# Motor-Board.net
KiCad netlist of a schematic drawn in EAGLE
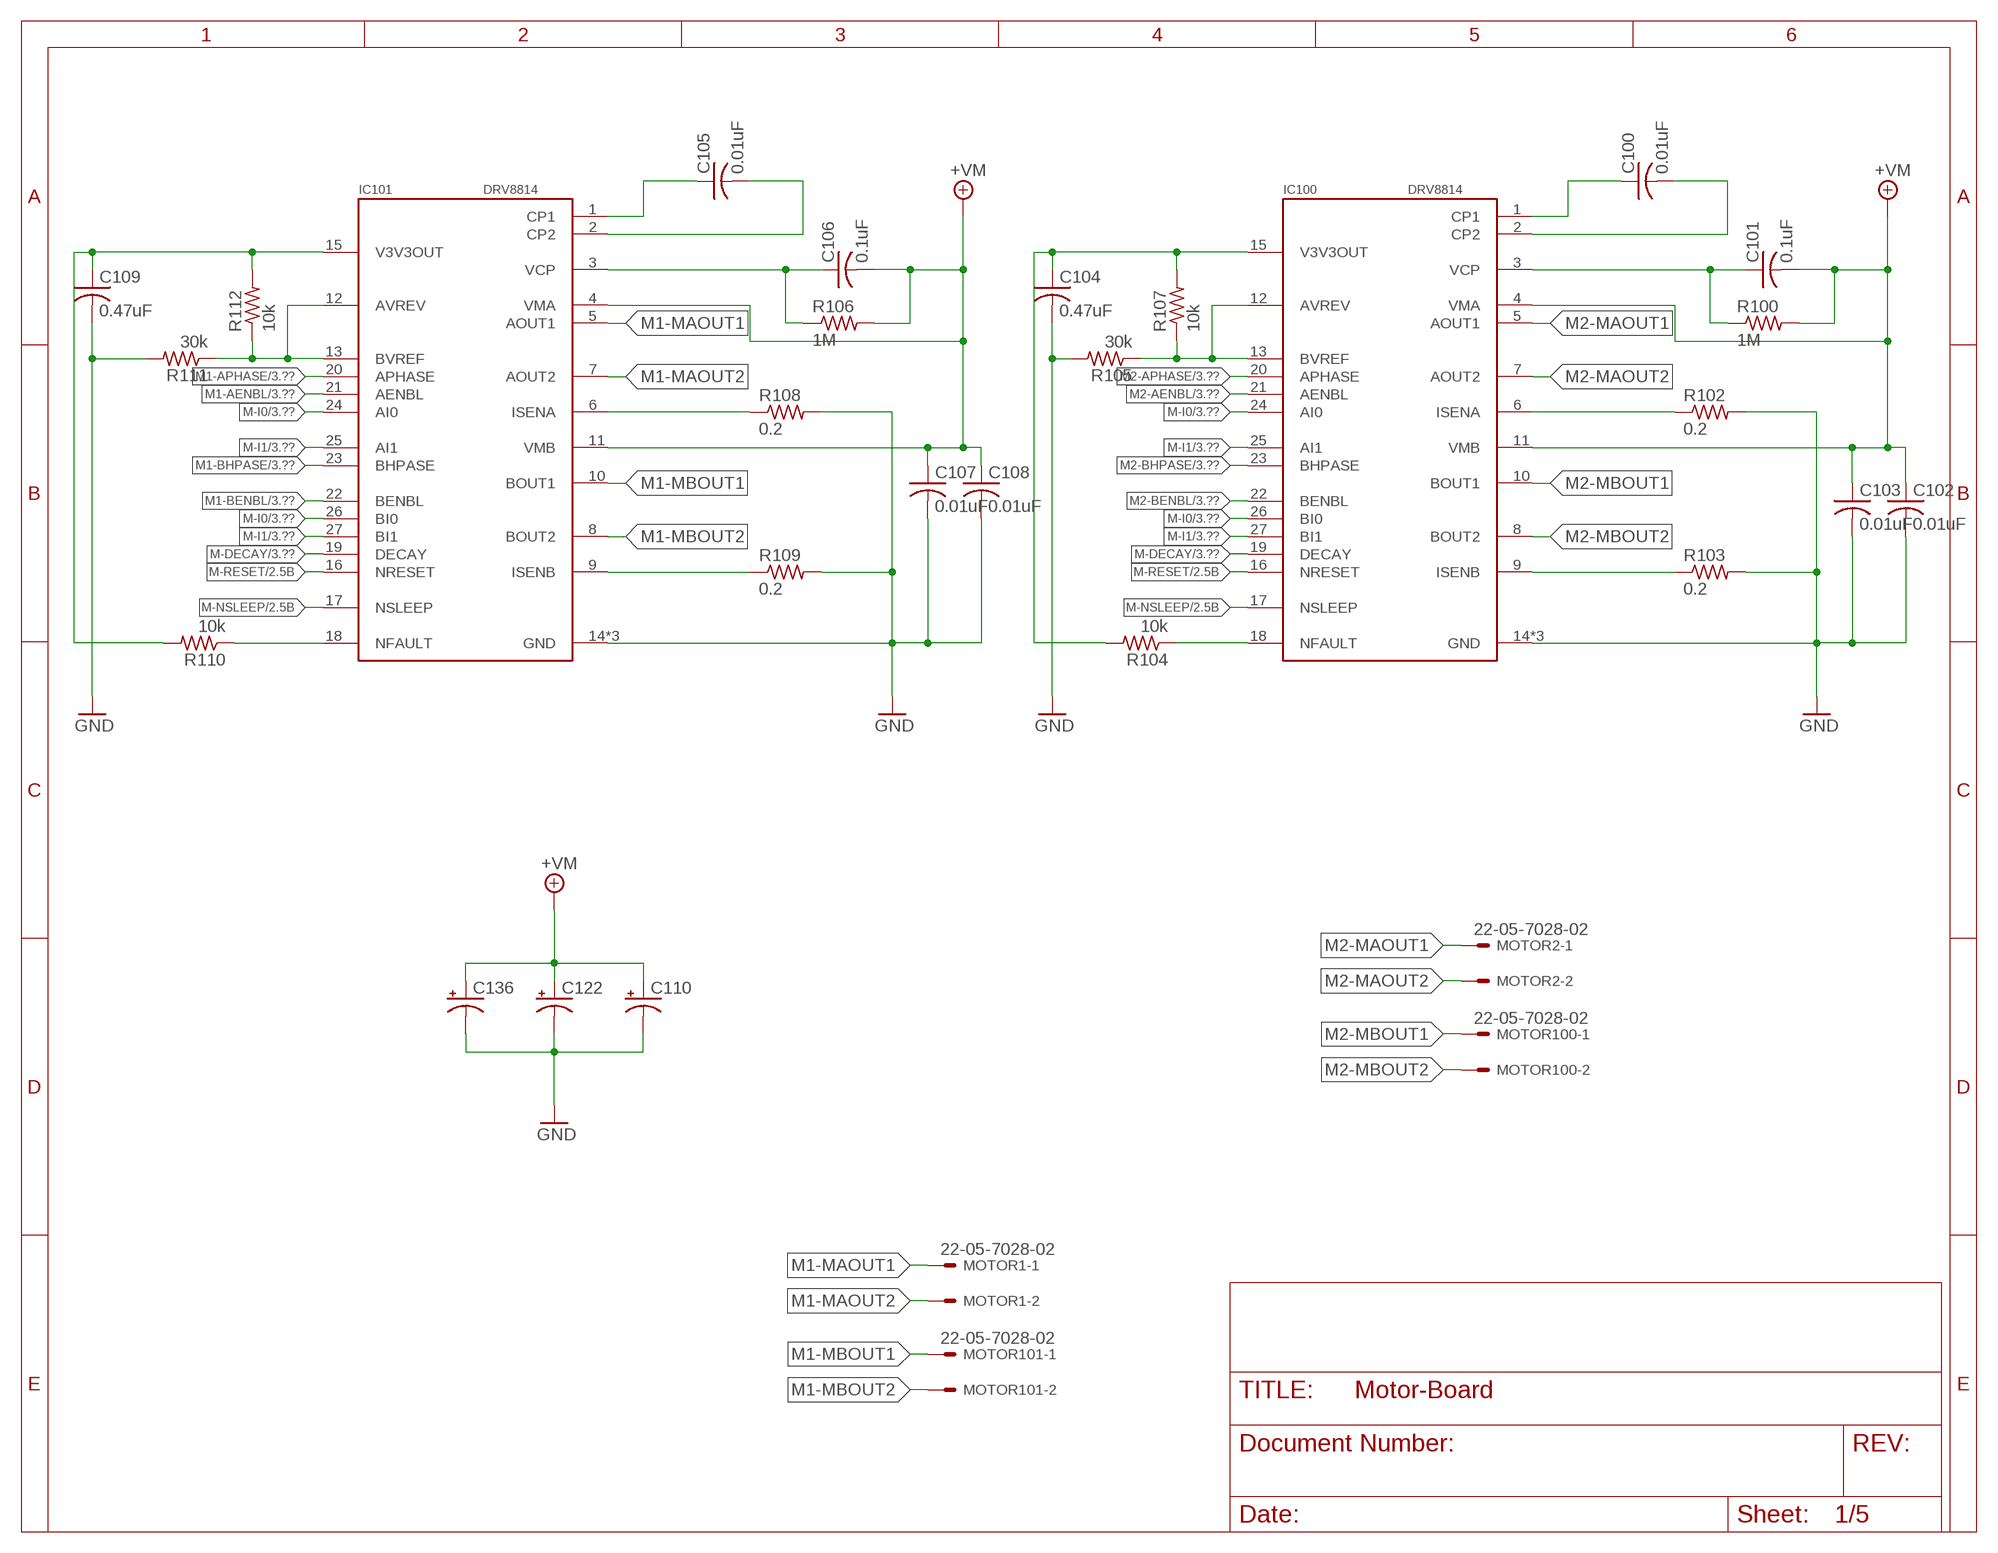
[diagram p0: schematic, sheet 1]
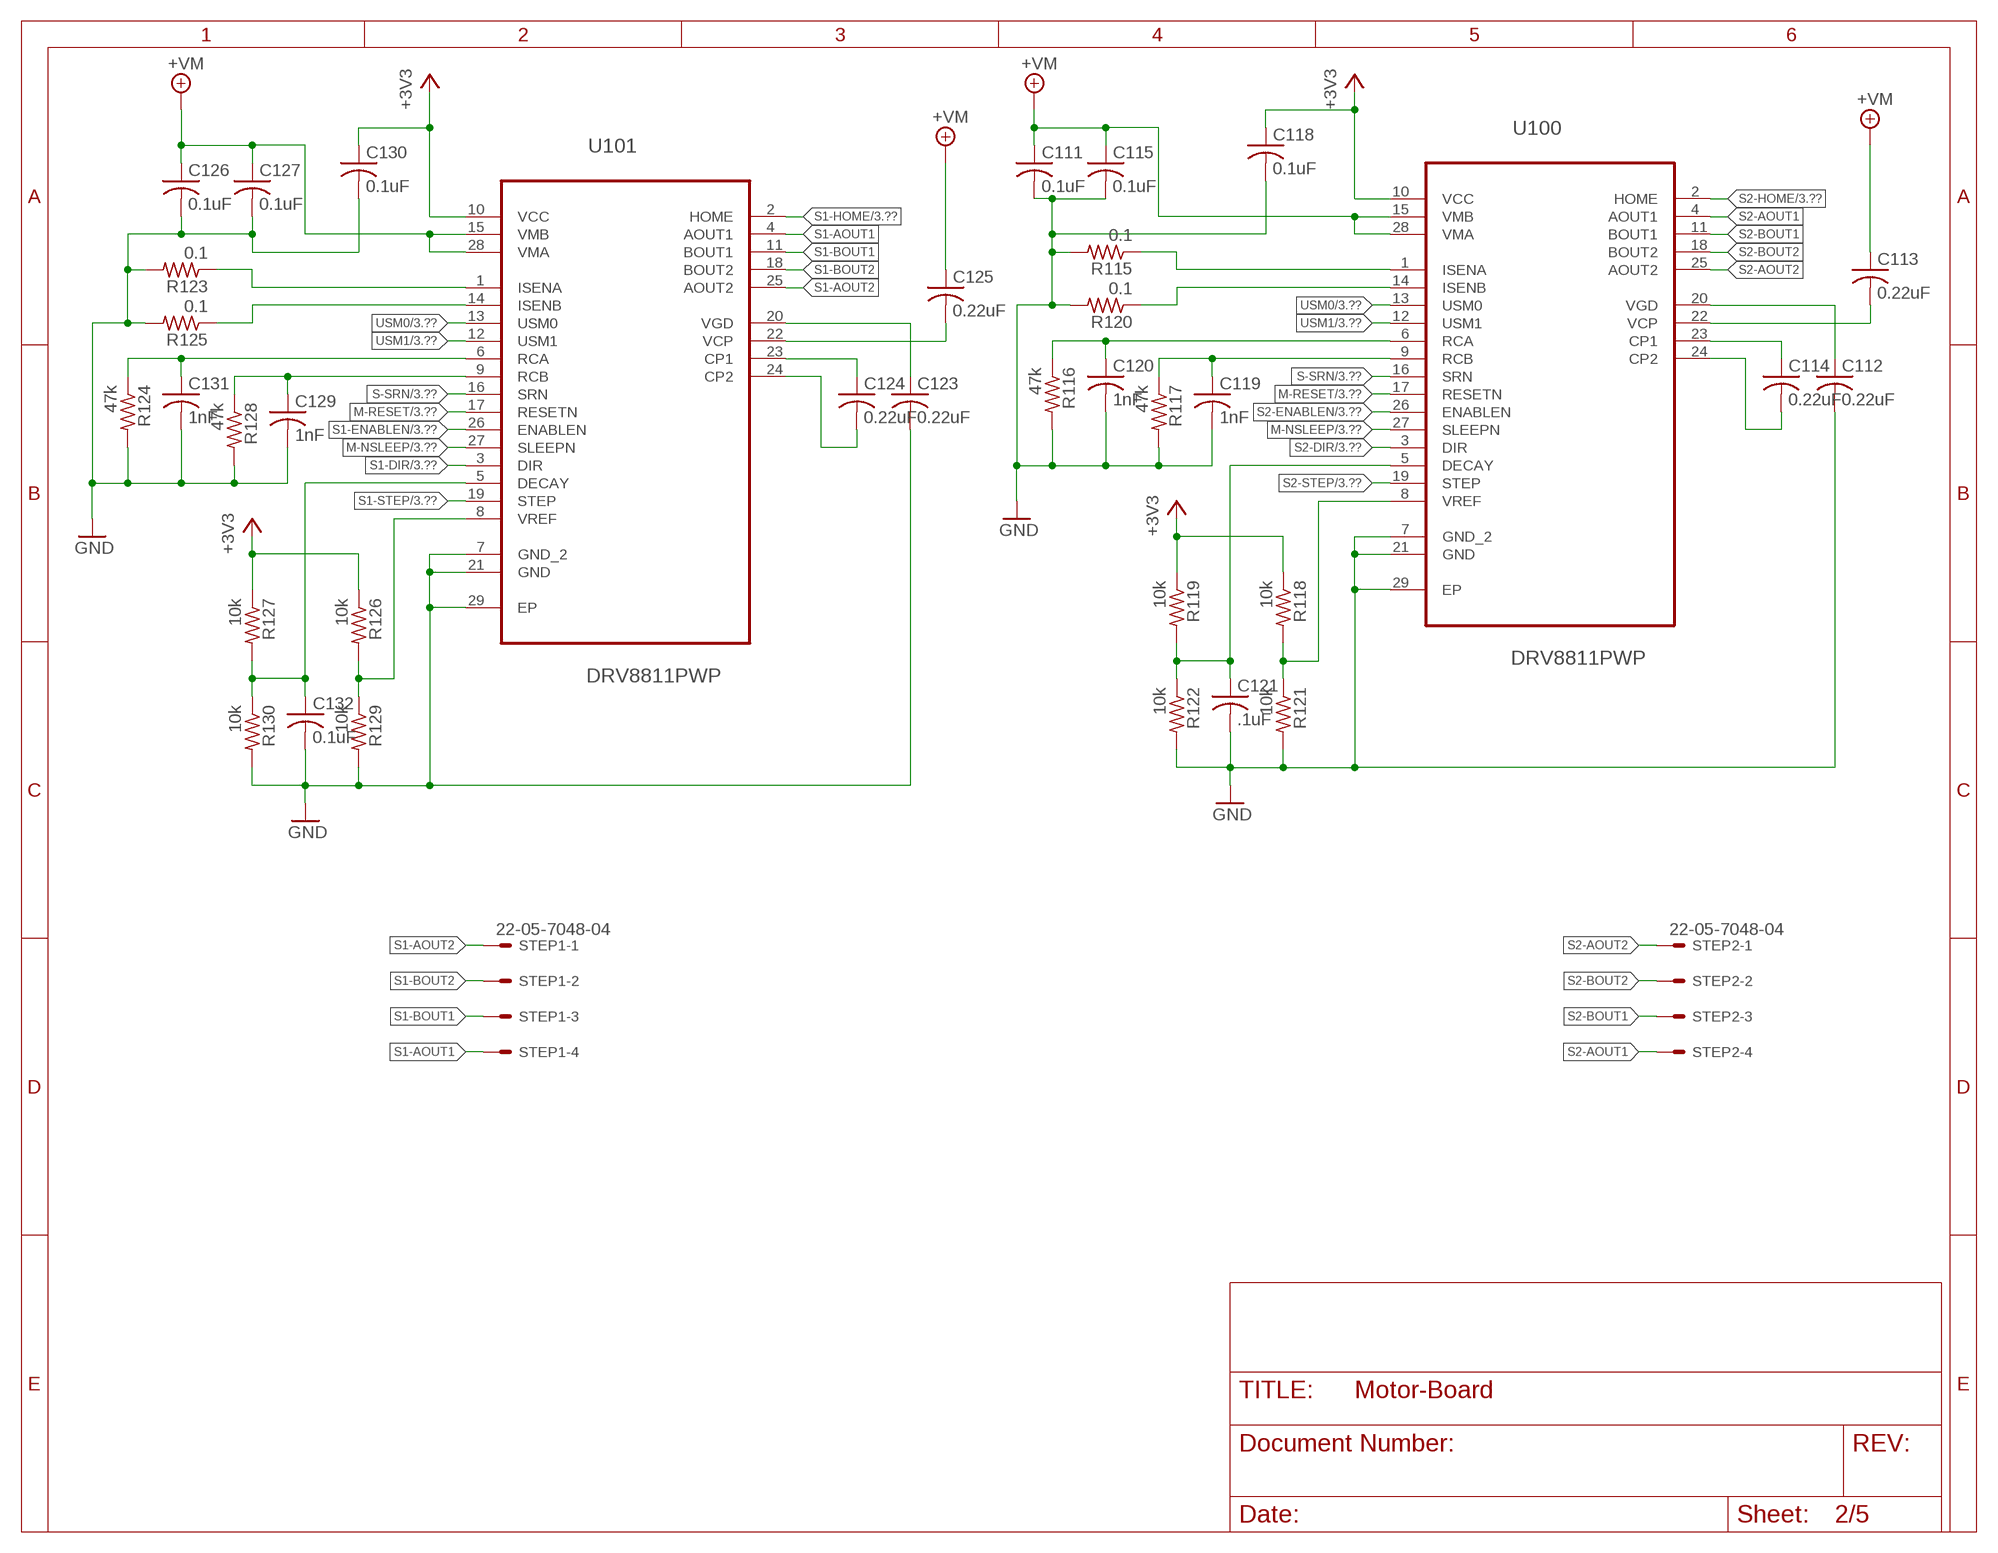
[diagram p1: schematic, sheet 2]
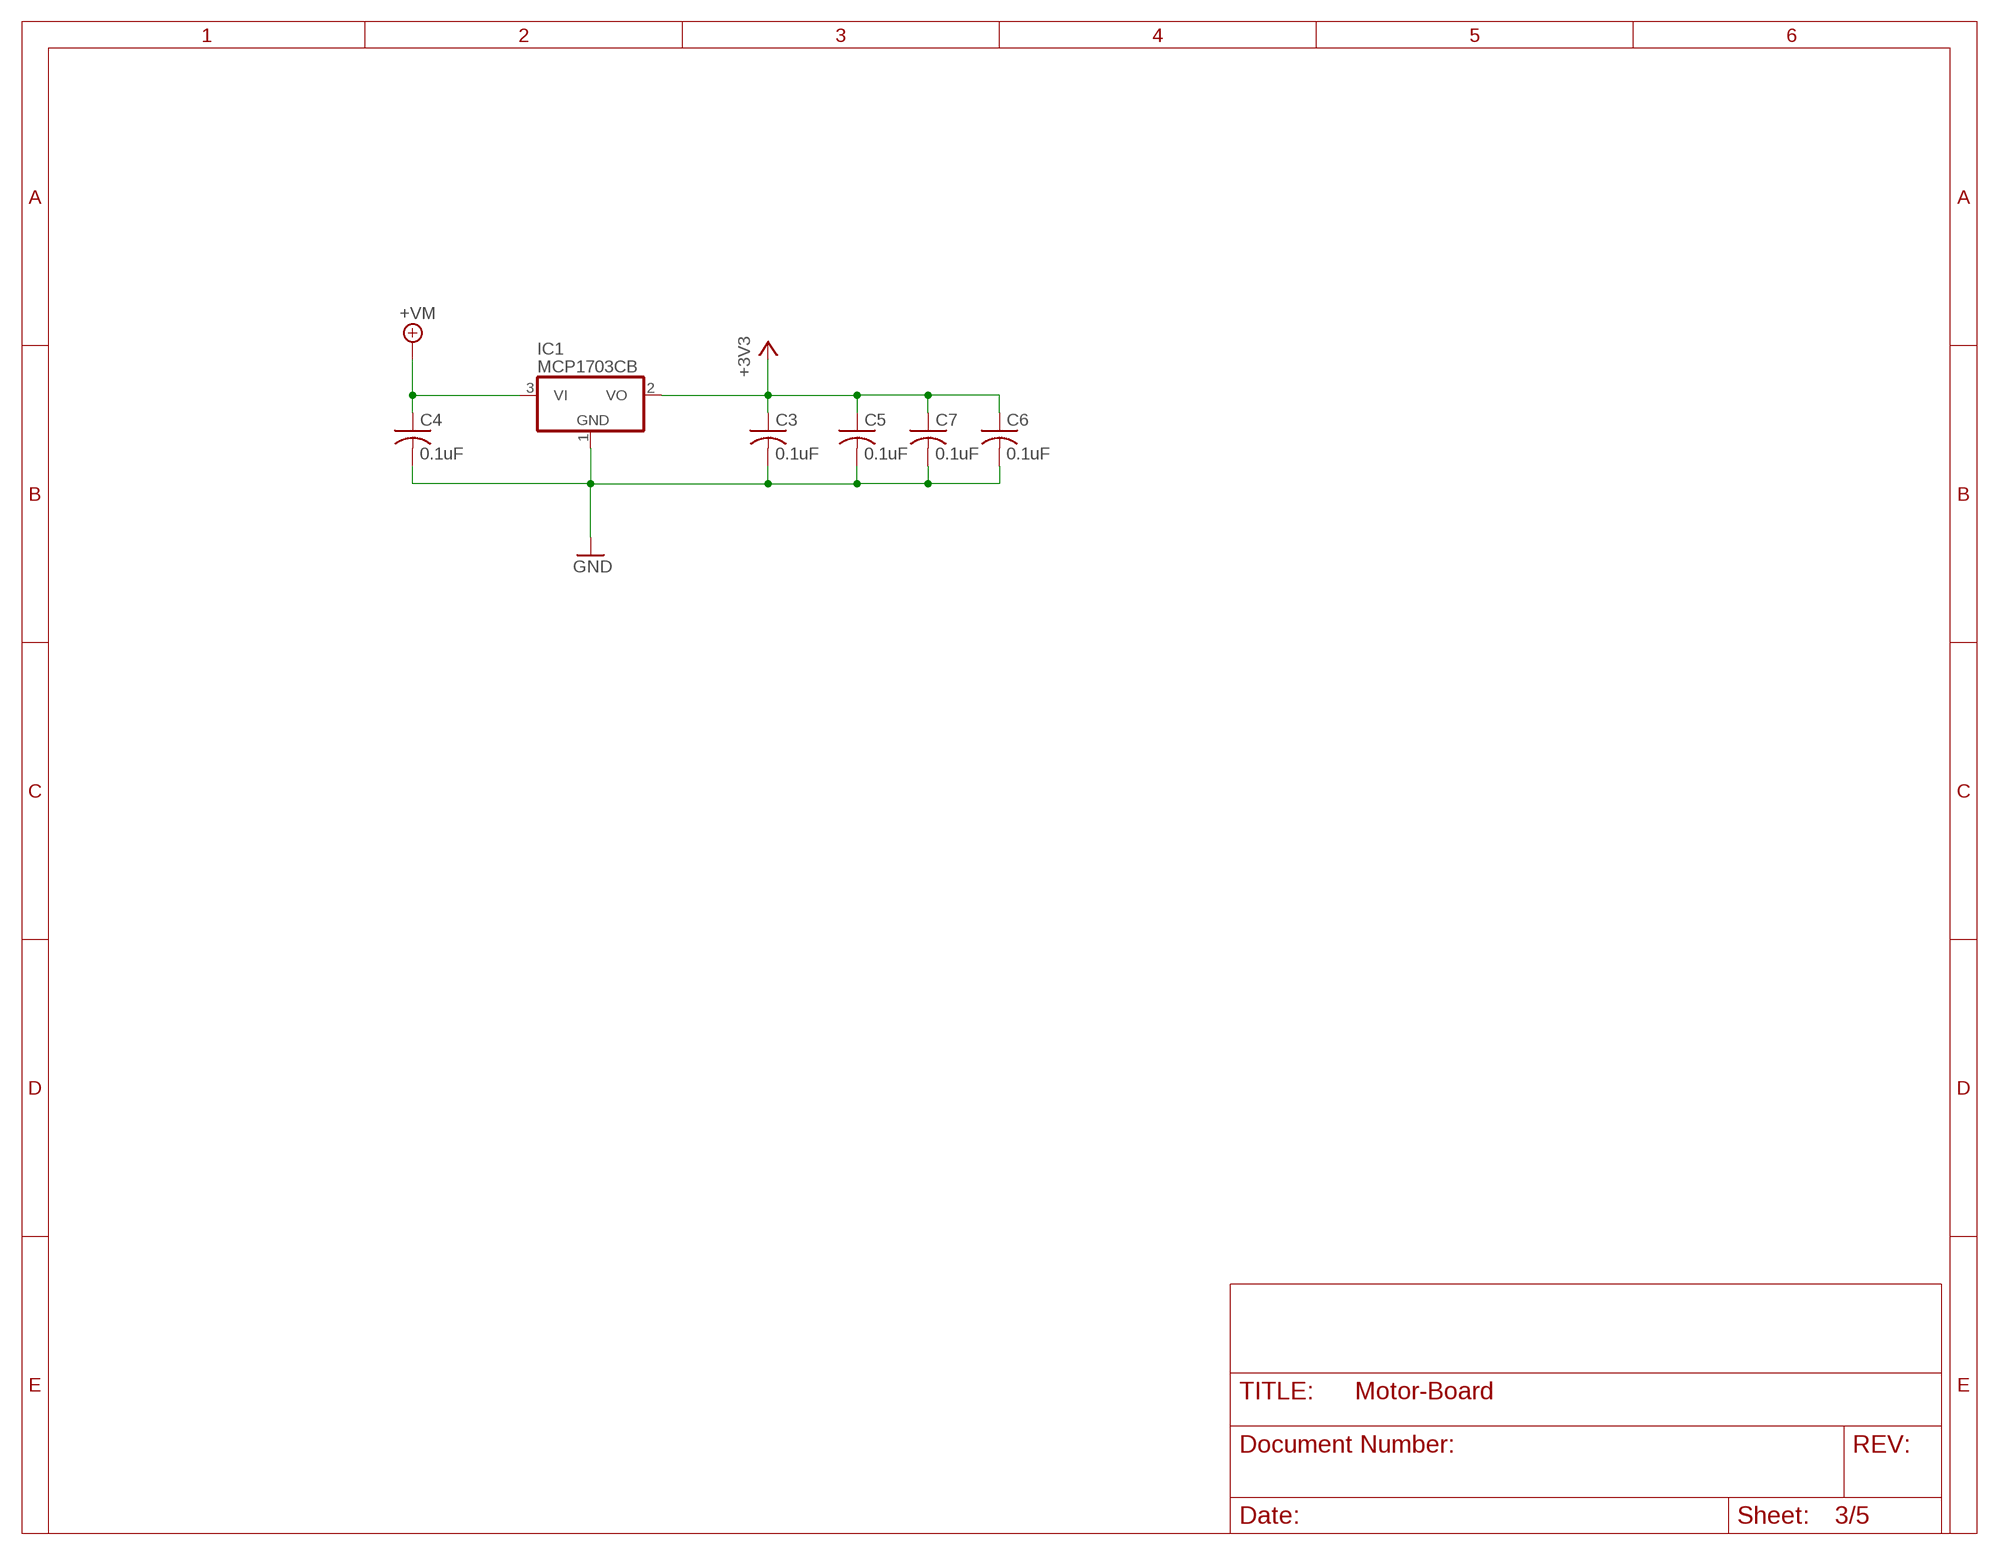
[diagram p2: schematic, sheet 3, part 1 of 2]
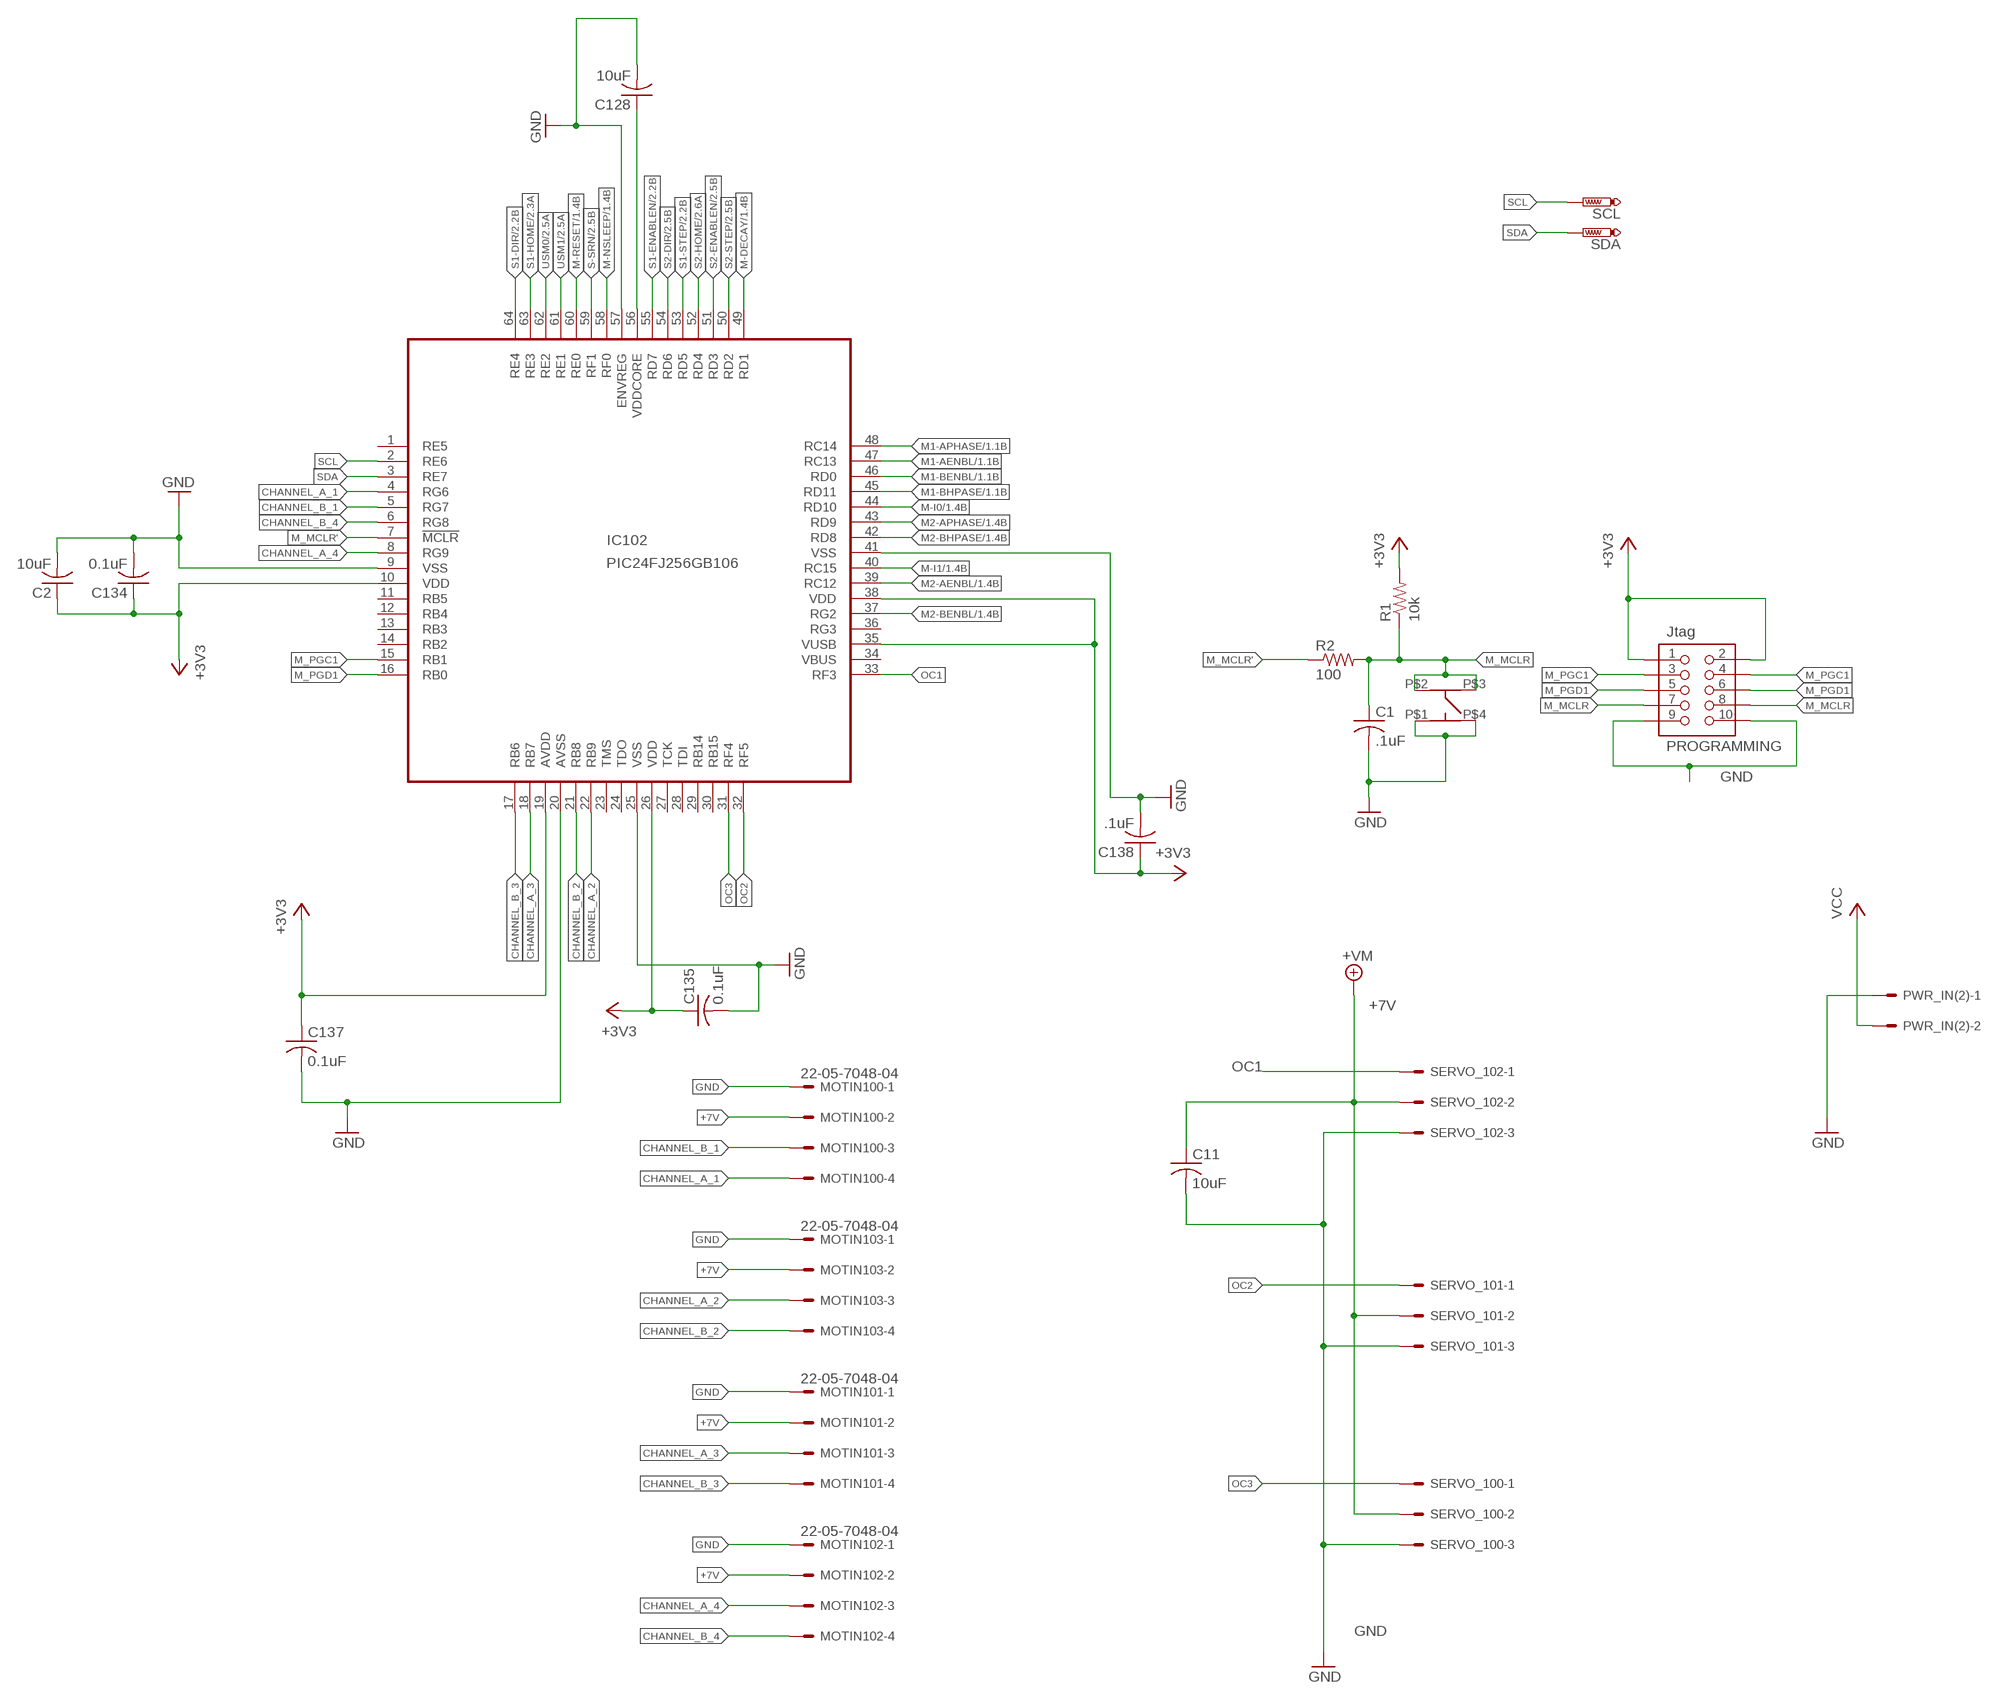
[diagram p3: schematic, sheet 3, part 2 of 2]
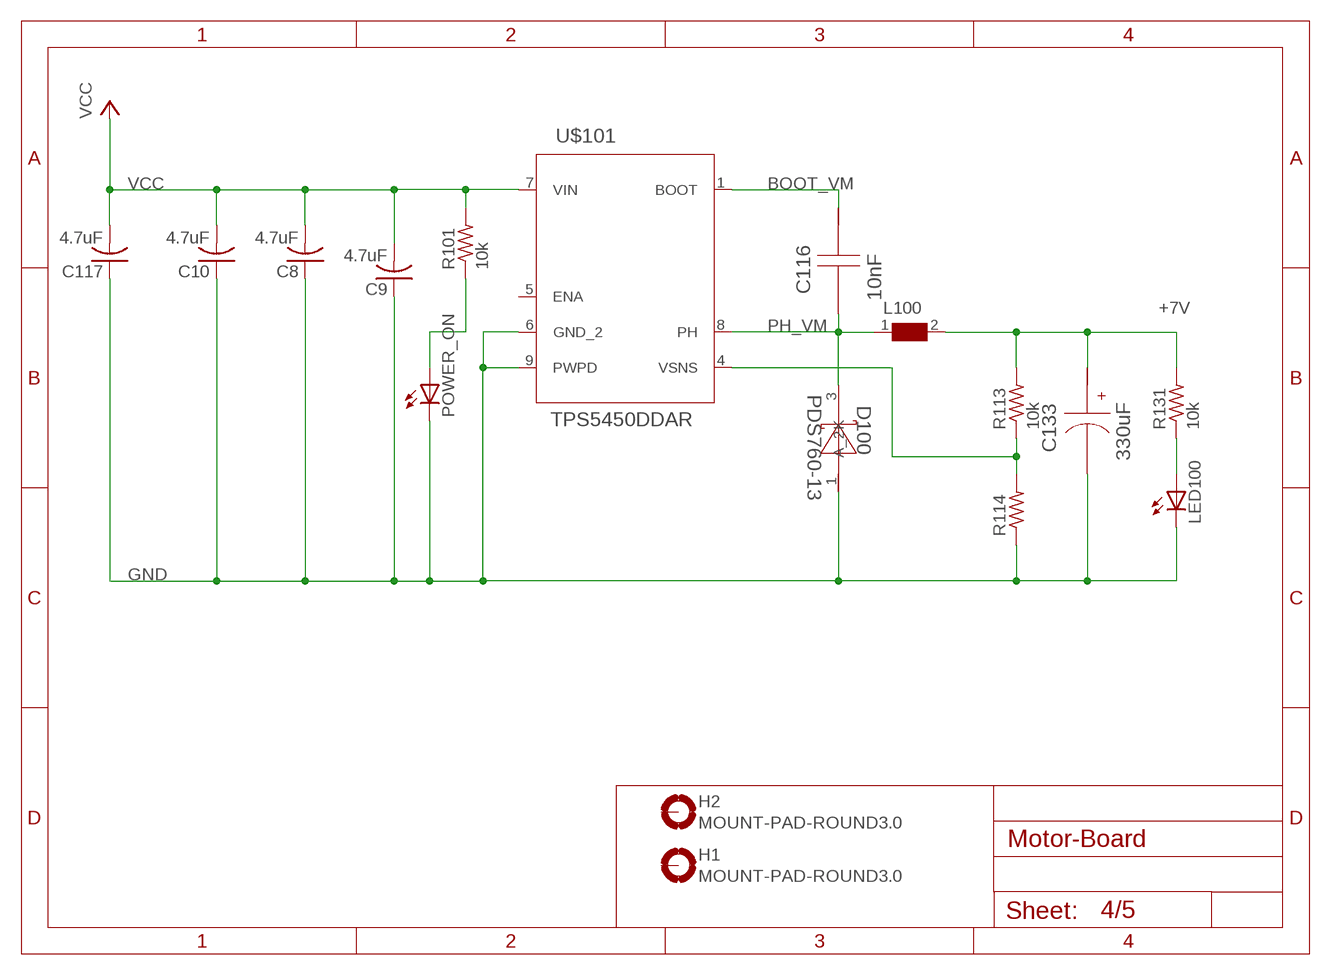
[diagram p4: schematic, sheet 4]

(export (version "E")
  (design (tool "Eeschema 10.0.6"))
  (components
    (comp (ref "C100")
      (value "0.01uF")
      (footprint "eagle-import:C0402")
      (libsource (lib "eagle-import") (part "C-USC0402"))
    )
    (comp (ref "C101")
      (value "0.1uF")
      (footprint "eagle-import:C0402")
      (libsource (lib "eagle-import") (part "C-USC0402"))
    )
    (comp (ref "C102")
      (value "0.01uF")
      (footprint "eagle-import:C0402")
      (libsource (lib "eagle-import") (part "C-USC0402"))
    )
    (comp (ref "C103")
      (value "0.01uF")
      (footprint "eagle-import:C0402")
      (libsource (lib "eagle-import") (part "C-USC0402"))
    )
    (comp (ref "C104")
      (value "0.47uF")
      (footprint "eagle-import:C0402")
      (libsource (lib "eagle-import") (part "C-USC0402"))
    )
    (comp (ref "C105")
      (value "0.01uF")
      (footprint "eagle-import:C0402")
      (libsource (lib "eagle-import") (part "C-USC0402"))
    )
    (comp (ref "C106")
      (value "0.1uF")
      (footprint "eagle-import:C0402")
      (libsource (lib "eagle-import") (part "C-USC0402"))
    )
    (comp (ref "C107")
      (value "0.01uF")
      (footprint "eagle-import:C0402")
      (libsource (lib "eagle-import") (part "C-USC0402"))
    )
    (comp (ref "C108")
      (value "0.01uF")
      (footprint "eagle-import:C0402")
      (libsource (lib "eagle-import") (part "C-USC0402"))
    )
    (comp (ref "C109")
      (value "0.47uF")
      (footprint "eagle-import:C0402")
      (libsource (lib "eagle-import") (part "C-USC0402"))
    )
    (comp (ref "C110")
      (value "CPOL-US153CLV-0605")
      (footprint "eagle-import:153CLV-0605")
      (libsource (lib "eagle-import") (part "CPOL-US153CLV-0605"))
    )
    (comp (ref "C122")
      (value "CPOL-US153CLV-0605")
      (footprint "eagle-import:153CLV-0605")
      (libsource (lib "eagle-import") (part "CPOL-US153CLV-0605"))
    )
    (comp (ref "C136")
      (value "CPOL-US153CLV-0605")
      (footprint "eagle-import:153CLV-0605")
      (libsource (lib "eagle-import") (part "CPOL-US153CLV-0605"))
    )
    (comp (ref "IC100")
      (value "DRV8814")
      (footprint "eagle-import:TSSOP-28")
      (libsource (lib "eagle-import") (part "DRV8818PWPR"))
    )
    (comp (ref "IC101")
      (value "DRV8814")
      (footprint "eagle-import:TSSOP-28")
      (libsource (lib "eagle-import") (part "DRV8818PWPR"))
    )
    (comp (ref "MOTOR1")
      (value "22-05-7028-02")
      (footprint "eagle-import:7395-02")
      (libsource (lib "eagle-import") (part "22-?-0205-7028"))
    )
    (comp (ref "MOTOR2")
      (value "22-05-7028-02")
      (footprint "eagle-import:7395-02")
      (libsource (lib "eagle-import") (part "22-?-0205-7028"))
    )
    (comp (ref "MOTOR100")
      (value "22-05-7028-02")
      (footprint "eagle-import:7395-02")
      (libsource (lib "eagle-import") (part "22-?-0205-7028"))
    )
    (comp (ref "MOTOR101")
      (value "22-05-7028-02")
      (footprint "eagle-import:7395-02")
      (libsource (lib "eagle-import") (part "22-?-0205-7028"))
    )
    (comp (ref "R100")
      (value "1M")
      (footprint "eagle-import:R0402")
      (libsource (lib "eagle-import") (part "R-US_R0402"))
    )
    (comp (ref "R102")
      (value "0.2")
      (footprint "eagle-import:R0402")
      (libsource (lib "eagle-import") (part "R-US_R0402"))
    )
    (comp (ref "R103")
      (value "0.2")
      (footprint "eagle-import:R0402")
      (libsource (lib "eagle-import") (part "R-US_R0402"))
    )
    (comp (ref "R104")
      (value "10k")
      (footprint "eagle-import:R0402")
      (libsource (lib "eagle-import") (part "R-US_R0402"))
    )
    (comp (ref "R105")
      (value "30k")
      (footprint "eagle-import:R0402")
      (libsource (lib "eagle-import") (part "R-US_R0402"))
    )
    (comp (ref "R106")
      (value "1M")
      (footprint "eagle-import:R0402")
      (libsource (lib "eagle-import") (part "R-US_R0402"))
    )
    (comp (ref "R107")
      (value "10k")
      (footprint "eagle-import:R0402")
      (libsource (lib "eagle-import") (part "R-US_R0402"))
    )
    (comp (ref "R108")
      (value "0.2")
      (footprint "eagle-import:R0402")
      (libsource (lib "eagle-import") (part "R-US_R0402"))
    )
    (comp (ref "R109")
      (value "0.2")
      (footprint "eagle-import:R0402")
      (libsource (lib "eagle-import") (part "R-US_R0402"))
    )
    (comp (ref "R110")
      (value "10k")
      (footprint "eagle-import:R0402")
      (libsource (lib "eagle-import") (part "R-US_R0402"))
    )
    (comp (ref "R111")
      (value "30k")
      (footprint "eagle-import:R0402")
      (libsource (lib "eagle-import") (part "R-US_R0402"))
    )
    (comp (ref "R112")
      (value "10k")
      (footprint "eagle-import:R0402")
      (libsource (lib "eagle-import") (part "R-US_R0402"))
    )
    (comp (ref "C8")
      (value "4.7uF")
      (footprint "eagle-import:C0805")
      (libsource (lib "eagle-import") (part "C-USC0805"))
    )
    (comp (ref "C9")
      (value "4.7uF")
      (footprint "eagle-import:C0805")
      (libsource (lib "eagle-import") (part "C-USC0805"))
    )
    (comp (ref "C10")
      (value "4.7uF")
      (footprint "eagle-import:C0805")
      (libsource (lib "eagle-import") (part "C-USC0805"))
    )
    (comp (ref "C116")
      (value "10nF")
      (footprint "eagle-import:0805")
      (fields (field (name "MANUFACTURER_PART_NUMBER") "C0805C103K5RACTU"))
      (libsource (lib "eagle-import") (part "C0805C103K5RACTU"))
    )
    (comp (ref "C117")
      (value "4.7uF")
      (footprint "eagle-import:C0805")
      (libsource (lib "eagle-import") (part "C-USC0805"))
    )
    (comp (ref "C133")
      (value "330uF")
      (footprint "eagle-import:SM_RADIAL_10AMM")
      (fields (field (name "MANUFACTURER_PART_NUMBER") "10SVP330MX"))
      (libsource (lib "eagle-import") (part "10SVP330MX"))
    )
    (comp (ref "D100")
      (value "PDS760-13")
      (footprint "eagle-import:POWERDI5")
      (libsource (lib "eagle-import") (part "PDS760-13"))
    )
    (comp (ref "H1")
      (value "MOUNT-PAD-ROUND3.0")
      (footprint "eagle-import:3,0-PAD")
      (libsource (lib "eagle-import") (part "MOUNT-PAD-ROUND3.0"))
    )
    (comp (ref "H2")
      (value "MOUNT-PAD-ROUND3.0")
      (footprint "eagle-import:3,0-PAD")
      (libsource (lib "eagle-import") (part "MOUNT-PAD-ROUND3.0"))
    )
    (comp (ref "L100")
      (value "WE-HCC-7443331000_1090")
      (footprint "eagle-import:WE-HCC_1090")
      (fields (field (name "MPN") "7443331000"))
      (libsource (lib "eagle-import") (part "WE-HCC_1090-7443331000"))
    )
    (comp (ref "LED100")
      (value "LEDCHIP-LED0603")
      (footprint "eagle-import:CHIP-LED0603")
      (libsource (lib "eagle-import") (part "LEDCHIP-LED0603"))
    )
    (comp (ref "POWER_ON")
      (value "LEDCHIP-LED0603")
      (footprint "eagle-import:CHIP-LED0603")
      (libsource (lib "eagle-import") (part "LEDCHIP-LED0603"))
    )
    (comp (ref "R101")
      (value "10k")
      (footprint "eagle-import:R0402")
      (libsource (lib "eagle-import") (part "R-US_R0402"))
    )
    (comp (ref "R113")
      (value "10k")
      (footprint "eagle-import:R0402")
      (libsource (lib "eagle-import") (part "R-US_R0402"))
    )
    (comp (ref "R114")
      (value "R-US_R0402")
      (footprint "eagle-import:R0402")
      (libsource (lib "eagle-import") (part "R-US_R0402"))
    )
    (comp (ref "R131")
      (value "10k")
      (footprint "eagle-import:R0402")
      (libsource (lib "eagle-import") (part "R-US_R0402"))
    )
    (comp (ref "U$101")
      (value "TPS5450DDAR")
      (footprint "eagle-import:R-PDSO-G8")
      (fields (field (name "MANUFACTURER_PART_NUMBER") "TPS5450DDA"))
      (libsource (lib "eagle-import") (part "TPS5450DDAR"))
    )
    (comp (ref "C1")
      (value ".1uF")
      (footprint "eagle-import:C0402")
      (libsource (lib "eagle-import") (part "C-USC0402"))
    )
    (comp (ref "C2")
      (value "10uF")
      (footprint "eagle-import:C0402")
      (libsource (lib "eagle-import") (part "C-USC0402"))
    )
    (comp (ref "C3")
      (value "0.1uF")
      (footprint "eagle-import:C0402")
      (libsource (lib "eagle-import") (part "C-USC0402"))
    )
    (comp (ref "C4")
      (value "0.1uF")
      (footprint "eagle-import:C0402")
      (libsource (lib "eagle-import") (part "C-USC0402"))
    )
    (comp (ref "C5")
      (value "0.1uF")
      (footprint "eagle-import:C0402")
      (libsource (lib "eagle-import") (part "C-USC0402"))
    )
    (comp (ref "C6")
      (value "0.1uF")
      (footprint "eagle-import:C0402")
      (libsource (lib "eagle-import") (part "C-USC0402"))
    )
    (comp (ref "C7")
      (value "0.1uF")
      (footprint "eagle-import:C0402")
      (libsource (lib "eagle-import") (part "C-USC0402"))
    )
    (comp (ref "C11")
      (value "10uF")
      (footprint "eagle-import:C0805")
      (libsource (lib "eagle-import") (part "C-USC0805"))
    )
    (comp (ref "C128")
      (value "10uF")
      (footprint "eagle-import:C0402")
      (libsource (lib "eagle-import") (part "C-USC0402"))
    )
    (comp (ref "C134")
      (value "0.1uF")
      (footprint "eagle-import:C0402")
      (libsource (lib "eagle-import") (part "C-USC0402"))
    )
    (comp (ref "C135")
      (value "0.1uF")
      (footprint "eagle-import:C0402")
      (libsource (lib "eagle-import") (part "C-USC0402"))
    )
    (comp (ref "C137")
      (value "0.1uF")
      (footprint "eagle-import:C0402")
      (libsource (lib "eagle-import") (part "C-USC0402"))
    )
    (comp (ref "C138")
      (value ".1uF")
      (footprint "eagle-import:C0402")
      (libsource (lib "eagle-import") (part "C-USC0402"))
    )
    (comp (ref "IC1")
      (value "MCP1703CB")
      (footprint "eagle-import:SOT23")
      (libsource (lib "eagle-import") (part "MCP1703CB"))
    )
    (comp (ref "IC102")
      (value "PIC24FJ256GB106")
      (footprint "eagle-import:TQFP64-10X10")
      (fields (field (name "MPN") "PIC24FJ256GB106-I/PT"))
      (libsource (lib "eagle-import") (part "PIC24FJ256GB106"))
    )
    (comp (ref "MOTIN100")
      (value "22-05-7048-04")
      (footprint "eagle-import:7395-04")
      (libsource (lib "eagle-import") (part "22-?-0405-7048"))
    )
    (comp (ref "MOTIN101")
      (value "22-05-7048-04")
      (footprint "eagle-import:7395-04")
      (libsource (lib "eagle-import") (part "22-?-0405-7048"))
    )
    (comp (ref "MOTIN102")
      (value "22-05-7048-04")
      (footprint "eagle-import:7395-04")
      (libsource (lib "eagle-import") (part "22-?-0405-7048"))
    )
    (comp (ref "MOTIN103")
      (value "22-05-7048-04")
      (footprint "eagle-import:7395-04")
      (libsource (lib "eagle-import") (part "22-?-0405-7048"))
    )
    (comp (ref "PROGRAMMING")
      (value "Jtag")
      (footprint "eagle-import:MOTHER-BOARD-REV5_10-PIN-SMD")
      (libsource (lib "eagle-import") (part "MOTHER-BOARD-REV5_PIN-CONNECTOR74089"))
    )
    (comp (ref "PWR_IN(2)")
      (value "555X-2H")
      (footprint "eagle-import:5569-2")
      (libsource (lib "eagle-import") (part "555X-2H"))
    )
    (comp (ref "R1")
      (value "10k")
      (footprint "eagle-import:R0402")
      (libsource (lib "eagle-import") (part "R-US_R0402"))
    )
    (comp (ref "R2")
      (value "100")
      (footprint "eagle-import:R0402")
      (libsource (lib "eagle-import") (part "R-US_R0402"))
    )
    (comp (ref "SCL")
      (value "PTR1B1,27")
      (footprint "eagle-import:B1,27")
      (libsource (lib "eagle-import") (part "PTR1B1,27"))
    )
    (comp (ref "SDA")
      (value "PTR1B1,27")
      (footprint "eagle-import:B1,27")
      (libsource (lib "eagle-import") (part "PTR1B1,27"))
    )
    (comp (ref "SERVO_100")
      (value "22-05-7038-03")
      (footprint "eagle-import:7395-03")
      (libsource (lib "eagle-import") (part "22-?-0305-7038"))
    )
    (comp (ref "SERVO_101")
      (value "22-05-7038-03")
      (footprint "eagle-import:7395-03")
      (libsource (lib "eagle-import") (part "22-?-0305-7038"))
    )
    (comp (ref "SERVO_102")
      (value "22-05-7038-03")
      (footprint "eagle-import:7395-03")
      (libsource (lib "eagle-import") (part "22-?-0305-7038"))
    )
    (comp (ref "U$100")
      (value "Switch3")
      (footprint "eagle-import:MC32882_FINAL")
      (libsource (lib "eagle-import") (part "MC32882_SW"))
    )
    (comp (ref "C111")
      (value "0.1uF")
      (footprint "eagle-import:C0402")
      (libsource (lib "eagle-import") (part "C-USC0402"))
    )
    (comp (ref "C112")
      (value "0.22uF")
      (footprint "eagle-import:C0402")
      (libsource (lib "eagle-import") (part "C-USC0402"))
    )
    (comp (ref "C113")
      (value "0.22uF")
      (footprint "eagle-import:C0402")
      (libsource (lib "eagle-import") (part "C-USC0402"))
    )
    (comp (ref "C114")
      (value "0.22uF")
      (footprint "eagle-import:C0402")
      (libsource (lib "eagle-import") (part "C-USC0402"))
    )
    (comp (ref "C115")
      (value "0.1uF")
      (footprint "eagle-import:C0402")
      (libsource (lib "eagle-import") (part "C-USC0402"))
    )
    (comp (ref "C118")
      (value "0.1uF")
      (footprint "eagle-import:C0402")
      (libsource (lib "eagle-import") (part "C-USC0402"))
    )
    (comp (ref "C119")
      (value "1nF")
      (footprint "eagle-import:C0402")
      (libsource (lib "eagle-import") (part "C-USC0402"))
    )
    (comp (ref "C120")
      (value "1nF")
      (footprint "eagle-import:C0402")
      (libsource (lib "eagle-import") (part "C-USC0402"))
    )
    (comp (ref "C121")
      (value ".1uF")
      (footprint "eagle-import:C0402")
      (libsource (lib "eagle-import") (part "C-USC0402"))
    )
    (comp (ref "C123")
      (value "0.22uF")
      (footprint "eagle-import:C0402")
      (libsource (lib "eagle-import") (part "C-USC0402"))
    )
    (comp (ref "C124")
      (value "0.22uF")
      (footprint "eagle-import:C0402")
      (libsource (lib "eagle-import") (part "C-USC0402"))
    )
    (comp (ref "C125")
      (value "0.22uF")
      (footprint "eagle-import:C0402")
      (libsource (lib "eagle-import") (part "C-USC0402"))
    )
    (comp (ref "C126")
      (value "0.1uF")
      (footprint "eagle-import:C0402")
      (libsource (lib "eagle-import") (part "C-USC0402"))
    )
    (comp (ref "C127")
      (value "0.1uF")
      (footprint "eagle-import:C0402")
      (libsource (lib "eagle-import") (part "C-USC0402"))
    )
    (comp (ref "C129")
      (value "1nF")
      (footprint "eagle-import:C0402")
      (libsource (lib "eagle-import") (part "C-USC0402"))
    )
    (comp (ref "C130")
      (value "0.1uF")
      (footprint "eagle-import:C0402")
      (libsource (lib "eagle-import") (part "C-USC0402"))
    )
    (comp (ref "C131")
      (value "1nF")
      (footprint "eagle-import:C0402")
      (libsource (lib "eagle-import") (part "C-USC0402"))
    )
    (comp (ref "C132")
      (value "0.1uF")
      (footprint "eagle-import:C0402")
      (libsource (lib "eagle-import") (part "C-USC0402"))
    )
    (comp (ref "R115")
      (value "0.1")
      (footprint "eagle-import:R0402")
      (libsource (lib "eagle-import") (part "R-US_R0402"))
    )
    (comp (ref "R116")
      (value "47k")
      (footprint "eagle-import:R0402")
      (libsource (lib "eagle-import") (part "R-US_R0402"))
    )
    (comp (ref "R117")
      (value "47k")
      (footprint "eagle-import:R0402")
      (libsource (lib "eagle-import") (part "R-US_R0402"))
    )
    (comp (ref "R118")
      (value "10k")
      (footprint "eagle-import:R0402")
      (libsource (lib "eagle-import") (part "R-US_R0402"))
    )
    (comp (ref "R119")
      (value "10k")
      (footprint "eagle-import:R0402")
      (libsource (lib "eagle-import") (part "R-US_R0402"))
    )
    (comp (ref "R120")
      (value "0.1")
      (footprint "eagle-import:R0402")
      (libsource (lib "eagle-import") (part "R-US_R0402"))
    )
    (comp (ref "R121")
      (value "10k")
      (footprint "eagle-import:R0402")
      (libsource (lib "eagle-import") (part "R-US_R0402"))
    )
    (comp (ref "R122")
      (value "10k")
      (footprint "eagle-import:R0402")
      (libsource (lib "eagle-import") (part "R-US_R0402"))
    )
    (comp (ref "R123")
      (value "0.1")
      (footprint "eagle-import:R0402")
      (libsource (lib "eagle-import") (part "R-US_R0402"))
    )
    (comp (ref "R124")
      (value "47k")
      (footprint "eagle-import:R0402")
      (libsource (lib "eagle-import") (part "R-US_R0402"))
    )
    (comp (ref "R125")
      (value "0.1")
      (footprint "eagle-import:R0402")
      (libsource (lib "eagle-import") (part "R-US_R0402"))
    )
    (comp (ref "R126")
      (value "10k")
      (footprint "eagle-import:R0402")
      (libsource (lib "eagle-import") (part "R-US_R0402"))
    )
    (comp (ref "R127")
      (value "10k")
      (footprint "eagle-import:R0402")
      (libsource (lib "eagle-import") (part "R-US_R0402"))
    )
    (comp (ref "R128")
      (value "47k")
      (footprint "eagle-import:R0402")
      (libsource (lib "eagle-import") (part "R-US_R0402"))
    )
    (comp (ref "R129")
      (value "10k")
      (footprint "eagle-import:R0402")
      (libsource (lib "eagle-import") (part "R-US_R0402"))
    )
    (comp (ref "R130")
      (value "10k")
      (footprint "eagle-import:R0402")
      (libsource (lib "eagle-import") (part "R-US_R0402"))
    )
    (comp (ref "STEP1")
      (value "22-05-7048-04")
      (footprint "eagle-import:7395-04")
      (libsource (lib "eagle-import") (part "22-?-0405-7048"))
    )
    (comp (ref "STEP2")
      (value "22-05-7048-04")
      (footprint "eagle-import:7395-04")
      (libsource (lib "eagle-import") (part "22-?-0405-7048"))
    )
    (comp (ref "U100")
      (value "DRV8811PWP")
      (footprint "eagle-import:SOP65P640X120-29N")
      (libsource (lib "eagle-import") (part "DRV8811PWP"))
    )
    (comp (ref "U101")
      (value "DRV8811PWP")
      (footprint "eagle-import:SOP65P640X120-29N")
      (libsource (lib "eagle-import") (part "DRV8811PWP"))
    )
  )
  (nets
    (net (code "1") (name "+3V3") (class "Default")
      (node (ref "C118") (pin "1") (pinfunction "1_1") (pintype "passive"))
      (node (ref "C130") (pin "1") (pinfunction "1_1") (pintype "passive"))
      (node (ref "C134") (pin "1") (pinfunction "1_1") (pintype "passive"))
      (node (ref "C135") (pin "1") (pinfunction "1_1") (pintype "passive"))
      (node (ref "C137") (pin "1") (pinfunction "1_1") (pintype "passive"))
      (node (ref "C138") (pin "1") (pinfunction "1_1") (pintype "passive"))
      (node (ref "C2") (pin "1") (pinfunction "1_1") (pintype "passive"))
      (node (ref "C3") (pin "1") (pinfunction "1_1") (pintype "passive"))
      (node (ref "C5") (pin "1") (pinfunction "1_1") (pintype "passive"))
      (node (ref "C6") (pin "1") (pinfunction "1_1") (pintype "passive"))
      (node (ref "C7") (pin "1") (pinfunction "1_1") (pintype "passive"))
      (node (ref "IC1") (pin "2") (pinfunction "VO_2") (pintype "passive"))
      (node (ref "IC102") (pin "10") (pinfunction "VDD_10") (pintype "power_in"))
      (node (ref "IC102") (pin "19") (pinfunction "AVDD_19") (pintype "power_in"))
      (node (ref "IC102") (pin "26") (pinfunction "VDD_26") (pintype "power_in"))
      (node (ref "IC102") (pin "35") (pinfunction "VUSB_35") (pintype "passive"))
      (node (ref "IC102") (pin "38") (pinfunction "VDD_38") (pintype "power_in"))
      (node (ref "PROGRAMMING") (pin "1") (pinfunction "P$1_1") (pintype "power_in"))
      (node (ref "PROGRAMMING") (pin "2") (pinfunction "P$2_2") (pintype "power_in"))
      (node (ref "R1") (pin "2") (pinfunction "2_2") (pintype "passive"))
      (node (ref "R118") (pin "1") (pinfunction "1_1") (pintype "passive"))
      (node (ref "R119") (pin "1") (pinfunction "1_1") (pintype "passive"))
      (node (ref "R126") (pin "1") (pinfunction "1_1") (pintype "passive"))
      (node (ref "R127") (pin "1") (pinfunction "1_1") (pintype "passive"))
      (node (ref "U100") (pin "10") (pinfunction "VCC_10") (pintype "power_in"))
      (node (ref "U101") (pin "10") (pinfunction "VCC_10") (pintype "power_in"))
    )
    (net (code "2") (name "+7V") (class "Default")
      (node (ref "C101") (pin "2") (pinfunction "2_2") (pintype "passive"))
      (node (ref "C102") (pin "1") (pinfunction "1_1") (pintype "passive"))
      (node (ref "C103") (pin "1") (pinfunction "1_1") (pintype "passive"))
      (node (ref "C106") (pin "2") (pinfunction "2_2") (pintype "passive"))
      (node (ref "C107") (pin "1") (pinfunction "1_1") (pintype "passive"))
      (node (ref "C108") (pin "1") (pinfunction "1_1") (pintype "passive"))
      (node (ref "C11") (pin "1") (pinfunction "1_1") (pintype "passive"))
      (node (ref "C110") (pin "+") (pinfunction "+_+") (pintype "passive"))
      (node (ref "C111") (pin "1") (pinfunction "1_1") (pintype "passive"))
      (node (ref "C113") (pin "1") (pinfunction "1_1") (pintype "passive"))
      (node (ref "C115") (pin "1") (pinfunction "1_1") (pintype "passive"))
      (node (ref "C122") (pin "+") (pinfunction "+_+") (pintype "passive"))
      (node (ref "C125") (pin "1") (pinfunction "1_1") (pintype "passive"))
      (node (ref "C126") (pin "1") (pinfunction "1_1") (pintype "passive"))
      (node (ref "C127") (pin "1") (pinfunction "1_1") (pintype "passive"))
      (node (ref "C133") (pin "1") (pinfunction "+_1") (pintype "passive"))
      (node (ref "C136") (pin "+") (pinfunction "+_+") (pintype "passive"))
      (node (ref "C4") (pin "1") (pinfunction "1_1") (pintype "passive"))
      (node (ref "IC1") (pin "3") (pinfunction "VI_3") (pintype "input"))
      (node (ref "IC100") (pin "11") (pinfunction "VMB_11") (pintype "output"))
      (node (ref "IC100") (pin "4") (pinfunction "VMA_4") (pintype "power_in"))
      (node (ref "IC101") (pin "11") (pinfunction "VMB_11") (pintype "output"))
      (node (ref "IC101") (pin "4") (pinfunction "VMA_4") (pintype "power_in"))
      (node (ref "L100") (pin "2") (pinfunction "2_2") (pintype "passive"))
      (node (ref "MOTIN100") (pin "2") (pinfunction "S_2") (pintype "passive"))
      (node (ref "MOTIN101") (pin "2") (pinfunction "S_2") (pintype "passive"))
      (node (ref "MOTIN102") (pin "2") (pinfunction "S_2") (pintype "passive"))
      (node (ref "MOTIN103") (pin "2") (pinfunction "S_2") (pintype "passive"))
      (node (ref "R100") (pin "2") (pinfunction "2_2") (pintype "passive"))
      (node (ref "R106") (pin "2") (pinfunction "2_2") (pintype "passive"))
      (node (ref "R113") (pin "2") (pinfunction "2_2") (pintype "passive"))
      (node (ref "R131") (pin "2") (pinfunction "2_2") (pintype "passive"))
      (node (ref "SERVO_100") (pin "2") (pinfunction "S_2") (pintype "passive"))
      (node (ref "SERVO_101") (pin "2") (pinfunction "S_2") (pintype "passive"))
      (node (ref "SERVO_102") (pin "2") (pinfunction "S_2") (pintype "passive"))
      (node (ref "U100") (pin "15") (pinfunction "VMB_15") (pintype "power_in"))
      (node (ref "U100") (pin "28") (pinfunction "VMA_28") (pintype "power_in"))
      (node (ref "U101") (pin "15") (pinfunction "VMB_15") (pintype "power_in"))
      (node (ref "U101") (pin "28") (pinfunction "VMA_28") (pintype "power_in"))
    )
    (net (code "3") (name "BOOT_VM") (class "Default")
      (node (ref "C116") (pin "1") (pinfunction "1_1") (pintype "passive"))
      (node (ref "U$101") (pin "1") (pinfunction "BOOT_1") (pintype "passive"))
    )
    (net (code "4") (name "CHANNEL_A_1") (class "Default")
      (node (ref "IC102") (pin "4") (pinfunction "RG6_4") (pintype "bidirectional"))
      (node (ref "MOTIN100") (pin "4") (pinfunction "S_4") (pintype "passive"))
    )
    (net (code "5") (name "CHANNEL_A_2") (class "Default")
      (node (ref "IC102") (pin "22") (pinfunction "RB9_22") (pintype "bidirectional"))
      (node (ref "MOTIN103") (pin "3") (pinfunction "S_3") (pintype "passive"))
    )
    (net (code "6") (name "CHANNEL_A_3") (class "Default")
      (node (ref "IC102") (pin "18") (pinfunction "RB7_18") (pintype "bidirectional"))
      (node (ref "MOTIN101") (pin "3") (pinfunction "S_3") (pintype "passive"))
    )
    (net (code "7") (name "CHANNEL_A_4") (class "Default")
      (node (ref "IC102") (pin "8") (pinfunction "RG9_8") (pintype "bidirectional"))
      (node (ref "MOTIN102") (pin "3") (pinfunction "S_3") (pintype "passive"))
    )
    (net (code "8") (name "CHANNEL_B_1") (class "Default")
      (node (ref "IC102") (pin "5") (pinfunction "RG7_5") (pintype "bidirectional"))
      (node (ref "MOTIN100") (pin "3") (pinfunction "S_3") (pintype "passive"))
    )
    (net (code "9") (name "CHANNEL_B_2") (class "Default")
      (node (ref "IC102") (pin "21") (pinfunction "RB8_21") (pintype "bidirectional"))
      (node (ref "MOTIN103") (pin "4") (pinfunction "S_4") (pintype "passive"))
    )
    (net (code "10") (name "CHANNEL_B_3") (class "Default")
      (node (ref "IC102") (pin "17") (pinfunction "RB6_17") (pintype "bidirectional"))
      (node (ref "MOTIN101") (pin "4") (pinfunction "S_4") (pintype "passive"))
    )
    (net (code "11") (name "CHANNEL_B_4") (class "Default")
      (node (ref "IC102") (pin "6") (pinfunction "RG8_6") (pintype "bidirectional"))
      (node (ref "MOTIN102") (pin "4") (pinfunction "S_4") (pintype "passive"))
    )
    (net (code "12") (name "GND") (class "Default")
      (node (ref "C1") (pin "2") (pinfunction "2_2") (pintype "passive"))
      (node (ref "C10") (pin "1") (pinfunction "1_1") (pintype "passive"))
      (node (ref "C102") (pin "2") (pinfunction "2_2") (pintype "passive"))
      (node (ref "C103") (pin "2") (pinfunction "2_2") (pintype "passive"))
      (node (ref "C104") (pin "2") (pinfunction "2_2") (pintype "passive"))
      (node (ref "C107") (pin "2") (pinfunction "2_2") (pintype "passive"))
      (node (ref "C108") (pin "2") (pinfunction "2_2") (pintype "passive"))
      (node (ref "C109") (pin "2") (pinfunction "2_2") (pintype "passive"))
      (node (ref "C11") (pin "2") (pinfunction "2_2") (pintype "passive"))
      (node (ref "C110") (pin "-") (pinfunction "-_-") (pintype "passive"))
      (node (ref "C111") (pin "2") (pinfunction "2_2") (pintype "passive"))
      (node (ref "C112") (pin "2") (pinfunction "2_2") (pintype "passive"))
      (node (ref "C115") (pin "2") (pinfunction "2_2") (pintype "passive"))
      (node (ref "C117") (pin "1") (pinfunction "1_1") (pintype "passive"))
      (node (ref "C118") (pin "2") (pinfunction "2_2") (pintype "passive"))
      (node (ref "C119") (pin "2") (pinfunction "2_2") (pintype "passive"))
      (node (ref "C120") (pin "2") (pinfunction "2_2") (pintype "passive"))
      (node (ref "C121") (pin "2") (pinfunction "2_2") (pintype "passive"))
      (node (ref "C122") (pin "-") (pinfunction "-_-") (pintype "passive"))
      (node (ref "C123") (pin "2") (pinfunction "2_2") (pintype "passive"))
      (node (ref "C126") (pin "2") (pinfunction "2_2") (pintype "passive"))
      (node (ref "C127") (pin "2") (pinfunction "2_2") (pintype "passive"))
      (node (ref "C128") (pin "2") (pinfunction "2_2") (pintype "passive"))
      (node (ref "C129") (pin "2") (pinfunction "2_2") (pintype "passive"))
      (node (ref "C130") (pin "2") (pinfunction "2_2") (pintype "passive"))
      (node (ref "C131") (pin "2") (pinfunction "2_2") (pintype "passive"))
      (node (ref "C132") (pin "2") (pinfunction "2_2") (pintype "passive"))
      (node (ref "C133") (pin "2") (pinfunction "-_2") (pintype "passive"))
      (node (ref "C134") (pin "2") (pinfunction "2_2") (pintype "passive"))
      (node (ref "C135") (pin "2") (pinfunction "2_2") (pintype "passive"))
      (node (ref "C136") (pin "-") (pinfunction "-_-") (pintype "passive"))
      (node (ref "C137") (pin "2") (pinfunction "2_2") (pintype "passive"))
      (node (ref "C138") (pin "2") (pinfunction "2_2") (pintype "passive"))
      (node (ref "C2") (pin "2") (pinfunction "2_2") (pintype "passive"))
      (node (ref "C3") (pin "2") (pinfunction "2_2") (pintype "passive"))
      (node (ref "C4") (pin "2") (pinfunction "2_2") (pintype "passive"))
      (node (ref "C5") (pin "2") (pinfunction "2_2") (pintype "passive"))
      (node (ref "C6") (pin "2") (pinfunction "2_2") (pintype "passive"))
      (node (ref "C7") (pin "2") (pinfunction "2_2") (pintype "passive"))
      (node (ref "C8") (pin "1") (pinfunction "1_1") (pintype "passive"))
      (node (ref "C9") (pin "1") (pinfunction "1_1") (pintype "passive"))
      (node (ref "D100") (pin "1") (pinfunction "A_2_1") (pintype "passive"))
      (node (ref "IC1") (pin "1") (pinfunction "GND_1") (pintype "passive"))
      (node (ref "IC100") (pin "14") (pinfunction "GND_14") (pintype "power_in"))
      (node (ref "IC100") (pin "28") (pinfunction "GND_28") (pintype "power_in"))
      (node (ref "IC100") (pin "EXP") (pinfunction "GND_EXP") (pintype "power_in"))
      (node (ref "IC101") (pin "14") (pinfunction "GND_14") (pintype "power_in"))
      (node (ref "IC101") (pin "28") (pinfunction "GND_28") (pintype "power_in"))
      (node (ref "IC101") (pin "EXP") (pinfunction "GND_EXP") (pintype "power_in"))
      (node (ref "IC102") (pin "20") (pinfunction "AVSS_20") (pintype "power_in"))
      (node (ref "IC102") (pin "25") (pinfunction "VSS_25") (pintype "power_in"))
      (node (ref "IC102") (pin "41") (pinfunction "VSS_41") (pintype "power_in"))
      (node (ref "IC102") (pin "57") (pinfunction "ENVREG_57") (pintype "passive"))
      (node (ref "IC102") (pin "9") (pinfunction "VSS_9") (pintype "power_in"))
      (node (ref "LED100") (pin "C") (pinfunction "C_C") (pintype "passive"))
      (node (ref "MOTIN100") (pin "1") (pinfunction "S_1") (pintype "passive"))
      (node (ref "MOTIN101") (pin "1") (pinfunction "S_1") (pintype "passive"))
      (node (ref "MOTIN102") (pin "1") (pinfunction "S_1") (pintype "passive"))
      (node (ref "MOTIN103") (pin "1") (pinfunction "S_1") (pintype "passive"))
      (node (ref "POWER_ON") (pin "C") (pinfunction "C_C") (pintype "passive"))
      (node (ref "PROGRAMMING") (pin "10") (pinfunction "P$10_10") (pintype "power_in"))
      (node (ref "PROGRAMMING") (pin "9") (pinfunction "P$9_9") (pintype "power_in"))
      (node (ref "PWR_IN(2)") (pin "1") (pinfunction "S_1") (pintype "passive"))
      (node (ref "R102") (pin "2") (pinfunction "2_2") (pintype "passive"))
      (node (ref "R103") (pin "2") (pinfunction "2_2") (pintype "passive"))
      (node (ref "R105") (pin "2") (pinfunction "2_2") (pintype "passive"))
      (node (ref "R108") (pin "2") (pinfunction "2_2") (pintype "passive"))
      (node (ref "R109") (pin "2") (pinfunction "2_2") (pintype "passive"))
      (node (ref "R111") (pin "2") (pinfunction "2_2") (pintype "passive"))
      (node (ref "R114") (pin "1") (pinfunction "1_1") (pintype "passive"))
      (node (ref "R115") (pin "2") (pinfunction "2_2") (pintype "passive"))
      (node (ref "R116") (pin "2") (pinfunction "2_2") (pintype "passive"))
      (node (ref "R117") (pin "2") (pinfunction "2_2") (pintype "passive"))
      (node (ref "R120") (pin "2") (pinfunction "2_2") (pintype "passive"))
      (node (ref "R121") (pin "2") (pinfunction "2_2") (pintype "passive"))
      (node (ref "R122") (pin "2") (pinfunction "2_2") (pintype "passive"))
      (node (ref "R123") (pin "2") (pinfunction "2_2") (pintype "passive"))
      (node (ref "R124") (pin "2") (pinfunction "2_2") (pintype "passive"))
      (node (ref "R125") (pin "2") (pinfunction "2_2") (pintype "passive"))
      (node (ref "R128") (pin "2") (pinfunction "2_2") (pintype "passive"))
      (node (ref "R129") (pin "2") (pinfunction "2_2") (pintype "passive"))
      (node (ref "R130") (pin "2") (pinfunction "2_2") (pintype "passive"))
      (node (ref "SERVO_100") (pin "3") (pinfunction "S_3") (pintype "passive"))
      (node (ref "SERVO_101") (pin "3") (pinfunction "S_3") (pintype "passive"))
      (node (ref "SERVO_102") (pin "3") (pinfunction "S_3") (pintype "passive"))
      (node (ref "U$100") (pin "P$1") (pinfunction "P1_P$1") (pintype "bidirectional"))
      (node (ref "U$100") (pin "P$4") (pinfunction "P4_P$4") (pintype "bidirectional"))
      (node (ref "U$101") (pin "6") (pinfunction "GND_2_6") (pintype "passive"))
      (node (ref "U$101") (pin "9") (pinfunction "PWPD_9") (pintype "passive"))
      (node (ref "U100") (pin "21") (pinfunction "GND_21") (pintype "passive"))
      (node (ref "U100") (pin "29") (pinfunction "EP_29") (pintype "passive"))
      (node (ref "U100") (pin "7") (pinfunction "GND_2_7") (pintype "passive"))
      (node (ref "U101") (pin "21") (pinfunction "GND_21") (pintype "passive"))
      (node (ref "U101") (pin "29") (pinfunction "EP_29") (pintype "passive"))
      (node (ref "U101") (pin "7") (pinfunction "GND_2_7") (pintype "passive"))
    )
    (net (code "13") (name "M-DECAY") (class "Default")
      (node (ref "IC100") (pin "19") (pinfunction "DECAY_19") (pintype "power_in"))
      (node (ref "IC101") (pin "19") (pinfunction "DECAY_19") (pintype "power_in"))
      (node (ref "IC102") (pin "49") (pinfunction "RD1_49") (pintype "bidirectional"))
    )
    (net (code "14") (name "M-I0") (class "Default")
      (node (ref "IC100") (pin "24") (pinfunction "AI0_24") (pintype "input"))
      (node (ref "IC100") (pin "26") (pinfunction "BI0_26") (pintype "input"))
      (node (ref "IC101") (pin "24") (pinfunction "AI0_24") (pintype "input"))
      (node (ref "IC101") (pin "26") (pinfunction "BI0_26") (pintype "input"))
      (node (ref "IC102") (pin "44") (pinfunction "RD10_44") (pintype "bidirectional"))
    )
    (net (code "15") (name "M-I1") (class "Default")
      (node (ref "IC100") (pin "25") (pinfunction "AI1_25") (pintype "input"))
      (node (ref "IC100") (pin "27") (pinfunction "BI1_27") (pintype "output"))
      (node (ref "IC101") (pin "25") (pinfunction "AI1_25") (pintype "input"))
      (node (ref "IC101") (pin "27") (pinfunction "BI1_27") (pintype "output"))
      (node (ref "IC102") (pin "40") (pinfunction "RC15_40") (pintype "bidirectional"))
    )
    (net (code "16") (name "M-NSLEEP") (class "Default")
      (node (ref "IC100") (pin "17") (pinfunction "NSLEEP_17") (pintype "passive"))
      (node (ref "IC101") (pin "17") (pinfunction "NSLEEP_17") (pintype "passive"))
      (node (ref "IC102") (pin "58") (pinfunction "RF0_58") (pintype "bidirectional"))
      (node (ref "U100") (pin "27") (pinfunction "SLEEPN_27") (pintype "input"))
      (node (ref "U101") (pin "27") (pinfunction "SLEEPN_27") (pintype "input"))
    )
    (net (code "17") (name "M-RESET") (class "Default")
      (node (ref "IC100") (pin "16") (pinfunction "NRESET_16") (pintype "passive"))
      (node (ref "IC101") (pin "16") (pinfunction "NRESET_16") (pintype "passive"))
      (node (ref "IC102") (pin "60") (pinfunction "RE0_60") (pintype "bidirectional"))
      (node (ref "U100") (pin "17") (pinfunction "RESETN_17") (pintype "input"))
      (node (ref "U101") (pin "17") (pinfunction "RESETN_17") (pintype "input"))
    )
    (net (code "18") (name "M1-AENBL") (class "Default")
      (node (ref "IC101") (pin "21") (pinfunction "AENBL_21") (pintype "input"))
      (node (ref "IC102") (pin "47") (pinfunction "RC13_47") (pintype "bidirectional"))
    )
    (net (code "19") (name "M1-APHASE") (class "Default")
      (node (ref "IC101") (pin "20") (pinfunction "APHASE_20") (pintype "input"))
      (node (ref "IC102") (pin "48") (pinfunction "RC14_48") (pintype "bidirectional"))
    )
    (net (code "20") (name "M1-BENBL") (class "Default")
      (node (ref "IC101") (pin "22") (pinfunction "BENBL_22") (pintype "input"))
      (node (ref "IC102") (pin "46") (pinfunction "RD0_46") (pintype "bidirectional"))
    )
    (net (code "21") (name "M1-BHPASE") (class "Default")
      (node (ref "IC101") (pin "23") (pinfunction "BHPASE_23") (pintype "input"))
      (node (ref "IC102") (pin "45") (pinfunction "RD11_45") (pintype "bidirectional"))
    )
    (net (code "22") (name "M1-MAOUT1") (class "Default")
      (node (ref "IC101") (pin "5") (pinfunction "AOUT1_5") (pintype "power_in"))
      (node (ref "MOTOR1") (pin "1") (pinfunction "S_1") (pintype "passive"))
    )
    (net (code "23") (name "M1-MAOUT2") (class "Default")
      (node (ref "IC101") (pin "7") (pinfunction "AOUT2_7") (pintype "output"))
      (node (ref "MOTOR1") (pin "2") (pinfunction "S_2") (pintype "passive"))
    )
    (net (code "24") (name "M1-MBOUT1") (class "Default")
      (node (ref "IC101") (pin "10") (pinfunction "BOUT1_10") (pintype "output"))
      (node (ref "MOTOR101") (pin "1") (pinfunction "S_1") (pintype "passive"))
    )
    (net (code "25") (name "M1-MBOUT2") (class "Default")
      (node (ref "IC101") (pin "8") (pinfunction "BOUT2_8") (pintype "passive"))
      (node (ref "MOTOR101") (pin "2") (pinfunction "S_2") (pintype "passive"))
    )
    (net (code "26") (name "M2-AENBL") (class "Default")
      (node (ref "IC100") (pin "21") (pinfunction "AENBL_21") (pintype "input"))
      (node (ref "IC102") (pin "39") (pinfunction "RC12_39") (pintype "bidirectional"))
    )
    (net (code "27") (name "M2-APHASE") (class "Default")
      (node (ref "IC100") (pin "20") (pinfunction "APHASE_20") (pintype "input"))
      (node (ref "IC102") (pin "43") (pinfunction "RD9_43") (pintype "bidirectional"))
    )
    (net (code "28") (name "M2-BENBL") (class "Default")
      (node (ref "IC100") (pin "22") (pinfunction "BENBL_22") (pintype "input"))
      (node (ref "IC102") (pin "37") (pinfunction "RG2_37") (pintype "bidirectional"))
    )
    (net (code "29") (name "M2-BHPASE") (class "Default")
      (node (ref "IC100") (pin "23") (pinfunction "BHPASE_23") (pintype "input"))
      (node (ref "IC102") (pin "42") (pinfunction "RD8_42") (pintype "bidirectional"))
    )
    (net (code "30") (name "M2-MAOUT1") (class "Default")
      (node (ref "IC100") (pin "5") (pinfunction "AOUT1_5") (pintype "power_in"))
      (node (ref "MOTOR2") (pin "1") (pinfunction "S_1") (pintype "passive"))
    )
    (net (code "31") (name "M2-MAOUT2") (class "Default")
      (node (ref "IC100") (pin "7") (pinfunction "AOUT2_7") (pintype "output"))
      (node (ref "MOTOR2") (pin "2") (pinfunction "S_2") (pintype "passive"))
    )
    (net (code "32") (name "M2-MBOUT1") (class "Default")
      (node (ref "IC100") (pin "10") (pinfunction "BOUT1_10") (pintype "output"))
      (node (ref "MOTOR100") (pin "1") (pinfunction "S_1") (pintype "passive"))
    )
    (net (code "33") (name "M2-MBOUT2") (class "Default")
      (node (ref "IC100") (pin "8") (pinfunction "BOUT2_8") (pintype "passive"))
      (node (ref "MOTOR100") (pin "2") (pinfunction "S_2") (pintype "passive"))
    )
    (net (code "34") (name "M_MCLR") (class "Default")
      (node (ref "C1") (pin "1") (pinfunction "1_1") (pintype "passive"))
      (node (ref "PROGRAMMING") (pin "7") (pinfunction "P$7_7") (pintype "power_in"))
      (node (ref "PROGRAMMING") (pin "8") (pinfunction "P$8_8") (pintype "power_in"))
      (node (ref "R1") (pin "1") (pinfunction "1_1") (pintype "passive"))
      (node (ref "R2") (pin "2") (pinfunction "2_2") (pintype "passive"))
      (node (ref "U$100") (pin "P$2") (pinfunction "P2_P$2") (pintype "bidirectional"))
      (node (ref "U$100") (pin "P$3") (pinfunction "P3_P$3") (pintype "bidirectional"))
    )
    (net (code "35") (name "M_MCLR'") (class "Default")
      (node (ref "IC102") (pin "7") (pinfunction "~{MCLR}_7") (pintype "bidirectional"))
      (node (ref "R2") (pin "1") (pinfunction "1_1") (pintype "passive"))
    )
    (net (code "36") (name "M_PGC1") (class "Default")
      (node (ref "IC102") (pin "15") (pinfunction "RB1_15") (pintype "bidirectional"))
      (node (ref "PROGRAMMING") (pin "3") (pinfunction "P$3_3") (pintype "power_in"))
      (node (ref "PROGRAMMING") (pin "4") (pinfunction "P$4_4") (pintype "power_in"))
    )
    (net (code "37") (name "M_PGD1") (class "Default")
      (node (ref "IC102") (pin "16") (pinfunction "RB0_16") (pintype "bidirectional"))
      (node (ref "PROGRAMMING") (pin "5") (pinfunction "P$5_5") (pintype "power_in"))
      (node (ref "PROGRAMMING") (pin "6") (pinfunction "P$6_6") (pintype "power_in"))
    )
    (net (code "38") (name "Net-(IC100-AVREV)") (class "Default")
      (node (ref "IC100") (pin "12") (pinfunction "AVREV_12") (pintype "passive"))
      (node (ref "IC100") (pin "13") (pinfunction "BVREF_13") (pintype "input"))
      (node (ref "R105") (pin "1") (pinfunction "1_1") (pintype "passive"))
      (node (ref "R107") (pin "1") (pinfunction "1_1") (pintype "passive"))
    )
    (net (code "39") (name "Net-(IC100-CP1)") (class "Default")
      (node (ref "C100") (pin "1") (pinfunction "1_1") (pintype "passive"))
      (node (ref "IC100") (pin "1") (pinfunction "CP1_1") (pintype "bidirectional"))
    )
    (net (code "40") (name "Net-(IC100-CP2)") (class "Default")
      (node (ref "C100") (pin "2") (pinfunction "2_2") (pintype "passive"))
      (node (ref "IC100") (pin "2") (pinfunction "CP2_2") (pintype "bidirectional"))
    )
    (net (code "41") (name "Net-(IC100-ISENA)") (class "Default")
      (node (ref "IC100") (pin "6") (pinfunction "ISENA_6") (pintype "output"))
      (node (ref "R102") (pin "1") (pinfunction "1_1") (pintype "passive"))
    )
    (net (code "42") (name "Net-(IC100-ISENB)") (class "Default")
      (node (ref "IC100") (pin "9") (pinfunction "ISENB_9") (pintype "passive"))
      (node (ref "R103") (pin "1") (pinfunction "1_1") (pintype "passive"))
    )
    (net (code "43") (name "Net-(IC100-NFAULT)") (class "Default")
      (node (ref "IC100") (pin "18") (pinfunction "NFAULT_18") (pintype "passive"))
      (node (ref "R104") (pin "1") (pinfunction "1_1") (pintype "passive"))
    )
    (net (code "44") (name "Net-(IC100-V3V3OUT)") (class "Default")
      (node (ref "C104") (pin "1") (pinfunction "1_1") (pintype "passive"))
      (node (ref "IC100") (pin "15") (pinfunction "V3V3OUT_15") (pintype "bidirectional"))
      (node (ref "R104") (pin "2") (pinfunction "2_2") (pintype "passive"))
      (node (ref "R107") (pin "2") (pinfunction "2_2") (pintype "passive"))
    )
    (net (code "45") (name "Net-(IC100-VCP)") (class "Default")
      (node (ref "C101") (pin "1") (pinfunction "1_1") (pintype "passive"))
      (node (ref "IC100") (pin "3") (pinfunction "VCP_3") (pintype "bidirectional"))
      (node (ref "R100") (pin "1") (pinfunction "1_1") (pintype "passive"))
    )
    (net (code "46") (name "Net-(IC101-AVREV)") (class "Default")
      (node (ref "IC101") (pin "12") (pinfunction "AVREV_12") (pintype "passive"))
      (node (ref "IC101") (pin "13") (pinfunction "BVREF_13") (pintype "input"))
      (node (ref "R111") (pin "1") (pinfunction "1_1") (pintype "passive"))
      (node (ref "R112") (pin "1") (pinfunction "1_1") (pintype "passive"))
    )
    (net (code "47") (name "Net-(IC101-CP1)") (class "Default")
      (node (ref "C105") (pin "1") (pinfunction "1_1") (pintype "passive"))
      (node (ref "IC101") (pin "1") (pinfunction "CP1_1") (pintype "bidirectional"))
    )
    (net (code "48") (name "Net-(IC101-CP2)") (class "Default")
      (node (ref "C105") (pin "2") (pinfunction "2_2") (pintype "passive"))
      (node (ref "IC101") (pin "2") (pinfunction "CP2_2") (pintype "bidirectional"))
    )
    (net (code "49") (name "Net-(IC101-ISENA)") (class "Default")
      (node (ref "IC101") (pin "6") (pinfunction "ISENA_6") (pintype "output"))
      (node (ref "R108") (pin "1") (pinfunction "1_1") (pintype "passive"))
    )
    (net (code "50") (name "Net-(IC101-ISENB)") (class "Default")
      (node (ref "IC101") (pin "9") (pinfunction "ISENB_9") (pintype "passive"))
      (node (ref "R109") (pin "1") (pinfunction "1_1") (pintype "passive"))
    )
    (net (code "51") (name "Net-(IC101-NFAULT)") (class "Default")
      (node (ref "IC101") (pin "18") (pinfunction "NFAULT_18") (pintype "passive"))
      (node (ref "R110") (pin "1") (pinfunction "1_1") (pintype "passive"))
    )
    (net (code "52") (name "Net-(IC101-V3V3OUT)") (class "Default")
      (node (ref "C109") (pin "1") (pinfunction "1_1") (pintype "passive"))
      (node (ref "IC101") (pin "15") (pinfunction "V3V3OUT_15") (pintype "bidirectional"))
      (node (ref "R110") (pin "2") (pinfunction "2_2") (pintype "passive"))
      (node (ref "R112") (pin "2") (pinfunction "2_2") (pintype "passive"))
    )
    (net (code "53") (name "Net-(IC101-VCP)") (class "Default")
      (node (ref "C106") (pin "1") (pinfunction "1_1") (pintype "passive"))
      (node (ref "IC101") (pin "3") (pinfunction "VCP_3") (pintype "bidirectional"))
      (node (ref "R106") (pin "1") (pinfunction "1_1") (pintype "passive"))
    )
    (net (code "54") (name "Net-(IC102-VDDCORE)") (class "Default")
      (node (ref "C128") (pin "1") (pinfunction "1_1") (pintype "passive"))
      (node (ref "IC102") (pin "56") (pinfunction "VDDCORE_56") (pintype "power_in"))
    )
    (net (code "55") (name "Net-(LED100-PadA)") (class "Default")
      (node (ref "LED100") (pin "A") (pinfunction "A_A") (pintype "passive"))
      (node (ref "R131") (pin "1") (pinfunction "1_1") (pintype "passive"))
    )
    (net (code "56") (name "Net-(POWER_ON-PadA)") (class "Default")
      (node (ref "POWER_ON") (pin "A") (pinfunction "A_A") (pintype "passive"))
      (node (ref "R101") (pin "1") (pinfunction "1_1") (pintype "passive"))
    )
    (net (code "57") (name "Net-(U$101-VSNS)") (class "Default")
      (node (ref "R113") (pin "1") (pinfunction "1_1") (pintype "passive"))
      (node (ref "R114") (pin "2") (pinfunction "2_2") (pintype "passive"))
      (node (ref "U$101") (pin "4") (pinfunction "VSNS_4") (pintype "passive"))
    )
    (net (code "58") (name "Net-(U100-CP1)") (class "Default")
      (node (ref "C114") (pin "1") (pinfunction "1_1") (pintype "passive"))
      (node (ref "U100") (pin "23") (pinfunction "CP1_23") (pintype "bidirectional"))
    )
    (net (code "59") (name "Net-(U100-CP2)") (class "Default")
      (node (ref "C114") (pin "2") (pinfunction "2_2") (pintype "passive"))
      (node (ref "U100") (pin "24") (pinfunction "CP2_24") (pintype "bidirectional"))
    )
    (net (code "60") (name "Net-(U100-DECAY)") (class "Default")
      (node (ref "C121") (pin "1") (pinfunction "1_1") (pintype "passive"))
      (node (ref "R119") (pin "2") (pinfunction "2_2") (pintype "passive"))
      (node (ref "R122") (pin "1") (pinfunction "1_1") (pintype "passive"))
      (node (ref "U100") (pin "5") (pinfunction "DECAY_5") (pintype "input"))
    )
    (net (code "61") (name "Net-(U100-ISENA)") (class "Default")
      (node (ref "R115") (pin "1") (pinfunction "1_1") (pintype "passive"))
      (node (ref "U100") (pin "1") (pinfunction "ISENA_1") (pintype "input"))
    )
    (net (code "62") (name "Net-(U100-ISENB)") (class "Default")
      (node (ref "R120") (pin "1") (pinfunction "1_1") (pintype "passive"))
      (node (ref "U100") (pin "14") (pinfunction "ISENB_14") (pintype "input"))
    )
    (net (code "63") (name "Net-(U100-RCA)") (class "Default")
      (node (ref "C120") (pin "1") (pinfunction "1_1") (pintype "passive"))
      (node (ref "R116") (pin "1") (pinfunction "1_1") (pintype "passive"))
      (node (ref "U100") (pin "6") (pinfunction "RCA_6") (pintype "input"))
    )
    (net (code "64") (name "Net-(U100-RCB)") (class "Default")
      (node (ref "C119") (pin "1") (pinfunction "1_1") (pintype "passive"))
      (node (ref "R117") (pin "1") (pinfunction "1_1") (pintype "passive"))
      (node (ref "U100") (pin "9") (pinfunction "RCB_9") (pintype "input"))
    )
    (net (code "65") (name "Net-(U100-VCP)") (class "Default")
      (node (ref "C113") (pin "2") (pinfunction "2_2") (pintype "passive"))
      (node (ref "U100") (pin "22") (pinfunction "VCP_22") (pintype "bidirectional"))
    )
    (net (code "66") (name "Net-(U100-VGD)") (class "Default")
      (node (ref "C112") (pin "1") (pinfunction "1_1") (pintype "passive"))
      (node (ref "U100") (pin "20") (pinfunction "VGD_20") (pintype "bidirectional"))
    )
    (net (code "67") (name "Net-(U100-VREF)") (class "Default")
      (node (ref "R118") (pin "2") (pinfunction "2_2") (pintype "passive"))
      (node (ref "R121") (pin "1") (pinfunction "1_1") (pintype "passive"))
      (node (ref "U100") (pin "8") (pinfunction "VREF_8") (pintype "input"))
    )
    (net (code "68") (name "Net-(U101-CP1)") (class "Default")
      (node (ref "C124") (pin "1") (pinfunction "1_1") (pintype "passive"))
      (node (ref "U101") (pin "23") (pinfunction "CP1_23") (pintype "bidirectional"))
    )
    (net (code "69") (name "Net-(U101-CP2)") (class "Default")
      (node (ref "C124") (pin "2") (pinfunction "2_2") (pintype "passive"))
      (node (ref "U101") (pin "24") (pinfunction "CP2_24") (pintype "bidirectional"))
    )
    (net (code "70") (name "Net-(U101-DECAY)") (class "Default")
      (node (ref "C132") (pin "1") (pinfunction "1_1") (pintype "passive"))
      (node (ref "R127") (pin "2") (pinfunction "2_2") (pintype "passive"))
      (node (ref "R130") (pin "1") (pinfunction "1_1") (pintype "passive"))
      (node (ref "U101") (pin "5") (pinfunction "DECAY_5") (pintype "input"))
    )
    (net (code "71") (name "Net-(U101-ISENA)") (class "Default")
      (node (ref "R123") (pin "1") (pinfunction "1_1") (pintype "passive"))
      (node (ref "U101") (pin "1") (pinfunction "ISENA_1") (pintype "input"))
    )
    (net (code "72") (name "Net-(U101-ISENB)") (class "Default")
      (node (ref "R125") (pin "1") (pinfunction "1_1") (pintype "passive"))
      (node (ref "U101") (pin "14") (pinfunction "ISENB_14") (pintype "input"))
    )
    (net (code "73") (name "Net-(U101-RCA)") (class "Default")
      (node (ref "C131") (pin "1") (pinfunction "1_1") (pintype "passive"))
      (node (ref "R124") (pin "1") (pinfunction "1_1") (pintype "passive"))
      (node (ref "U101") (pin "6") (pinfunction "RCA_6") (pintype "input"))
    )
    (net (code "74") (name "Net-(U101-RCB)") (class "Default")
      (node (ref "C129") (pin "1") (pinfunction "1_1") (pintype "passive"))
      (node (ref "R128") (pin "1") (pinfunction "1_1") (pintype "passive"))
      (node (ref "U101") (pin "9") (pinfunction "RCB_9") (pintype "input"))
    )
    (net (code "75") (name "Net-(U101-VCP)") (class "Default")
      (node (ref "C125") (pin "2") (pinfunction "2_2") (pintype "passive"))
      (node (ref "U101") (pin "22") (pinfunction "VCP_22") (pintype "bidirectional"))
    )
    (net (code "76") (name "Net-(U101-VGD)") (class "Default")
      (node (ref "C123") (pin "1") (pinfunction "1_1") (pintype "passive"))
      (node (ref "U101") (pin "20") (pinfunction "VGD_20") (pintype "bidirectional"))
    )
    (net (code "77") (name "Net-(U101-VREF)") (class "Default")
      (node (ref "R126") (pin "2") (pinfunction "2_2") (pintype "passive"))
      (node (ref "R129") (pin "1") (pinfunction "1_1") (pintype "passive"))
      (node (ref "U101") (pin "8") (pinfunction "VREF_8") (pintype "input"))
    )
    (net (code "78") (name "OC1") (class "Default")
      (node (ref "IC102") (pin "33") (pinfunction "RF3_33") (pintype "bidirectional"))
      (node (ref "SERVO_102") (pin "1") (pinfunction "S_1") (pintype "passive"))
    )
    (net (code "79") (name "OC2") (class "Default")
      (node (ref "IC102") (pin "32") (pinfunction "RF5_32") (pintype "bidirectional"))
      (node (ref "SERVO_101") (pin "1") (pinfunction "S_1") (pintype "passive"))
    )
    (net (code "80") (name "OC3") (class "Default")
      (node (ref "IC102") (pin "31") (pinfunction "RF4_31") (pintype "bidirectional"))
      (node (ref "SERVO_100") (pin "1") (pinfunction "S_1") (pintype "passive"))
    )
    (net (code "81") (name "PH_VM") (class "Default")
      (node (ref "C116") (pin "2") (pinfunction "2_2") (pintype "passive"))
      (node (ref "D100") (pin "3") (pinfunction "K_3") (pintype "passive"))
      (node (ref "L100") (pin "1") (pinfunction "1_1") (pintype "passive"))
      (node (ref "U$101") (pin "8") (pinfunction "PH_8") (pintype "passive"))
    )
    (net (code "82") (name "S-SRN") (class "Default")
      (node (ref "IC102") (pin "59") (pinfunction "RF1_59") (pintype "bidirectional"))
      (node (ref "U100") (pin "16") (pinfunction "SRN_16") (pintype "input"))
      (node (ref "U101") (pin "16") (pinfunction "SRN_16") (pintype "input"))
    )
    (net (code "83") (name "S1-AOUT1") (class "Default")
      (node (ref "STEP1") (pin "4") (pinfunction "S_4") (pintype "passive"))
      (node (ref "U101") (pin "4") (pinfunction "AOUT1_4") (pintype "output"))
    )
    (net (code "84") (name "S1-AOUT2") (class "Default")
      (node (ref "STEP1") (pin "1") (pinfunction "S_1") (pintype "passive"))
      (node (ref "U101") (pin "25") (pinfunction "AOUT2_25") (pintype "output"))
    )
    (net (code "85") (name "S1-BOUT1") (class "Default")
      (node (ref "STEP1") (pin "3") (pinfunction "S_3") (pintype "passive"))
      (node (ref "U101") (pin "11") (pinfunction "BOUT1_11") (pintype "output"))
    )
    (net (code "86") (name "S1-BOUT2") (class "Default")
      (node (ref "STEP1") (pin "2") (pinfunction "S_2") (pintype "passive"))
      (node (ref "U101") (pin "18") (pinfunction "BOUT2_18") (pintype "output"))
    )
    (net (code "87") (name "S1-DIR") (class "Default")
      (node (ref "IC102") (pin "64") (pinfunction "RE4_64") (pintype "bidirectional"))
      (node (ref "U101") (pin "3") (pinfunction "DIR_3") (pintype "input"))
    )
    (net (code "88") (name "S1-ENABLEN") (class "Default")
      (node (ref "IC102") (pin "55") (pinfunction "RD7_55") (pintype "bidirectional"))
      (node (ref "U101") (pin "26") (pinfunction "ENABLEN_26") (pintype "input"))
    )
    (net (code "89") (name "S1-HOME") (class "Default")
      (node (ref "IC102") (pin "63") (pinfunction "RE3_63") (pintype "bidirectional"))
      (node (ref "U101") (pin "2") (pinfunction "HOME_2") (pintype "output"))
    )
    (net (code "90") (name "S1-STEP") (class "Default")
      (node (ref "IC102") (pin "53") (pinfunction "RD5_53") (pintype "bidirectional"))
      (node (ref "U101") (pin "19") (pinfunction "STEP_19") (pintype "input"))
    )
    (net (code "91") (name "S2-AOUT1") (class "Default")
      (node (ref "STEP2") (pin "4") (pinfunction "S_4") (pintype "passive"))
      (node (ref "U100") (pin "4") (pinfunction "AOUT1_4") (pintype "output"))
    )
    (net (code "92") (name "S2-AOUT2") (class "Default")
      (node (ref "STEP2") (pin "1") (pinfunction "S_1") (pintype "passive"))
      (node (ref "U100") (pin "25") (pinfunction "AOUT2_25") (pintype "output"))
    )
    (net (code "93") (name "S2-BOUT1") (class "Default")
      (node (ref "STEP2") (pin "3") (pinfunction "S_3") (pintype "passive"))
      (node (ref "U100") (pin "11") (pinfunction "BOUT1_11") (pintype "output"))
    )
    (net (code "94") (name "S2-BOUT2") (class "Default")
      (node (ref "STEP2") (pin "2") (pinfunction "S_2") (pintype "passive"))
      (node (ref "U100") (pin "18") (pinfunction "BOUT2_18") (pintype "output"))
    )
    (net (code "95") (name "S2-DIR") (class "Default")
      (node (ref "IC102") (pin "54") (pinfunction "RD6_54") (pintype "bidirectional"))
      (node (ref "U100") (pin "3") (pinfunction "DIR_3") (pintype "input"))
    )
    (net (code "96") (name "S2-ENABLEN") (class "Default")
      (node (ref "IC102") (pin "51") (pinfunction "RD3_51") (pintype "bidirectional"))
      (node (ref "U100") (pin "26") (pinfunction "ENABLEN_26") (pintype "input"))
    )
    (net (code "97") (name "S2-HOME") (class "Default")
      (node (ref "IC102") (pin "52") (pinfunction "RD4_52") (pintype "bidirectional"))
      (node (ref "U100") (pin "2") (pinfunction "HOME_2") (pintype "output"))
    )
    (net (code "98") (name "S2-STEP") (class "Default")
      (node (ref "IC102") (pin "50") (pinfunction "RD2_50") (pintype "bidirectional"))
      (node (ref "U100") (pin "19") (pinfunction "STEP_19") (pintype "input"))
    )
    (net (code "99") (name "SCL") (class "Default")
      (node (ref "IC102") (pin "2") (pinfunction "RE6_2") (pintype "bidirectional"))
      (node (ref "SCL") (pin "TP") (pinfunction "TP_TP") (pintype "input"))
    )
    (net (code "100") (name "SDA") (class "Default")
      (node (ref "IC102") (pin "3") (pinfunction "RE7_3") (pintype "bidirectional"))
      (node (ref "SDA") (pin "TP") (pinfunction "TP_TP") (pintype "input"))
    )
    (net (code "101") (name "USM0") (class "Default")
      (node (ref "IC102") (pin "62") (pinfunction "RE2_62") (pintype "bidirectional"))
      (node (ref "U100") (pin "13") (pinfunction "USM0_13") (pintype "input"))
      (node (ref "U101") (pin "13") (pinfunction "USM0_13") (pintype "input"))
    )
    (net (code "102") (name "USM1") (class "Default")
      (node (ref "IC102") (pin "61") (pinfunction "RE1_61") (pintype "bidirectional"))
      (node (ref "U100") (pin "12") (pinfunction "USM1_12") (pintype "input"))
      (node (ref "U101") (pin "12") (pinfunction "USM1_12") (pintype "input"))
    )
    (net (code "103") (name "VCC") (class "Default")
      (node (ref "C10") (pin "2") (pinfunction "2_2") (pintype "passive"))
      (node (ref "C117") (pin "2") (pinfunction "2_2") (pintype "passive"))
      (node (ref "C8") (pin "2") (pinfunction "2_2") (pintype "passive"))
      (node (ref "C9") (pin "2") (pinfunction "2_2") (pintype "passive"))
      (node (ref "PWR_IN(2)") (pin "2") (pinfunction "S_2") (pintype "passive"))
      (node (ref "R101") (pin "2") (pinfunction "2_2") (pintype "passive"))
      (node (ref "U$101") (pin "7") (pinfunction "VIN_7") (pintype "passive"))
    )
    (net (code "104") (name "unconnected-(H1-MOUNT-PadB3,0)") (class "Default")
      (node (ref "H1") (pin "B3,0") (pinfunction "MOUNT_B3,0") (pintype "passive"))
    )
    (net (code "105") (name "unconnected-(H2-MOUNT-PadB3,0)") (class "Default")
      (node (ref "H2") (pin "B3,0") (pinfunction "MOUNT_B3,0") (pintype "passive"))
    )
    (net (code "106") (name "unconnected-(IC102-RB2-Pad14)") (class "Default")
      (node (ref "IC102") (pin "14") (pinfunction "RB2_14") (pintype "bidirectional"))
    )
    (net (code "107") (name "unconnected-(IC102-RB3-Pad13)") (class "Default")
      (node (ref "IC102") (pin "13") (pinfunction "RB3_13") (pintype "bidirectional"))
    )
    (net (code "108") (name "unconnected-(IC102-RB4-Pad12)") (class "Default")
      (node (ref "IC102") (pin "12") (pinfunction "RB4_12") (pintype "bidirectional"))
    )
    (net (code "109") (name "unconnected-(IC102-RB5-Pad11)") (class "Default")
      (node (ref "IC102") (pin "11") (pinfunction "RB5_11") (pintype "bidirectional"))
    )
    (net (code "110") (name "unconnected-(IC102-RB14-Pad29)") (class "Default")
      (node (ref "IC102") (pin "29") (pinfunction "RB14_29") (pintype "bidirectional"))
    )
    (net (code "111") (name "unconnected-(IC102-RB15-Pad30)") (class "Default")
      (node (ref "IC102") (pin "30") (pinfunction "RB15_30") (pintype "bidirectional"))
    )
    (net (code "112") (name "unconnected-(IC102-RE5-Pad1)") (class "Default")
      (node (ref "IC102") (pin "1") (pinfunction "RE5_1") (pintype "bidirectional"))
    )
    (net (code "113") (name "unconnected-(IC102-RG3-Pad36)") (class "Default")
      (node (ref "IC102") (pin "36") (pinfunction "RG3_36") (pintype "bidirectional"))
    )
    (net (code "114") (name "unconnected-(IC102-TCK-Pad27)") (class "Default")
      (node (ref "IC102") (pin "27") (pinfunction "TCK_27") (pintype "input"))
    )
    (net (code "115") (name "unconnected-(IC102-TDI-Pad28)") (class "Default")
      (node (ref "IC102") (pin "28") (pinfunction "TDI_28") (pintype "input"))
    )
    (net (code "116") (name "unconnected-(IC102-TDO-Pad24)") (class "Default")
      (node (ref "IC102") (pin "24") (pinfunction "TDO_24") (pintype "output"))
    )
    (net (code "117") (name "unconnected-(IC102-TMS-Pad23)") (class "Default")
      (node (ref "IC102") (pin "23") (pinfunction "TMS_23") (pintype "input"))
    )
    (net (code "118") (name "unconnected-(IC102-VBUS-Pad34)") (class "Default")
      (node (ref "IC102") (pin "34") (pinfunction "VBUS_34") (pintype "passive"))
    )
    (net (code "119") (name "unconnected-(U$101-ENA-Pad5)") (class "Default")
      (node (ref "U$101") (pin "5") (pinfunction "ENA_5") (pintype "passive"))
    )
  )
)
